# prism.net
KiCad netlist of a schematic drawn in EAGLE
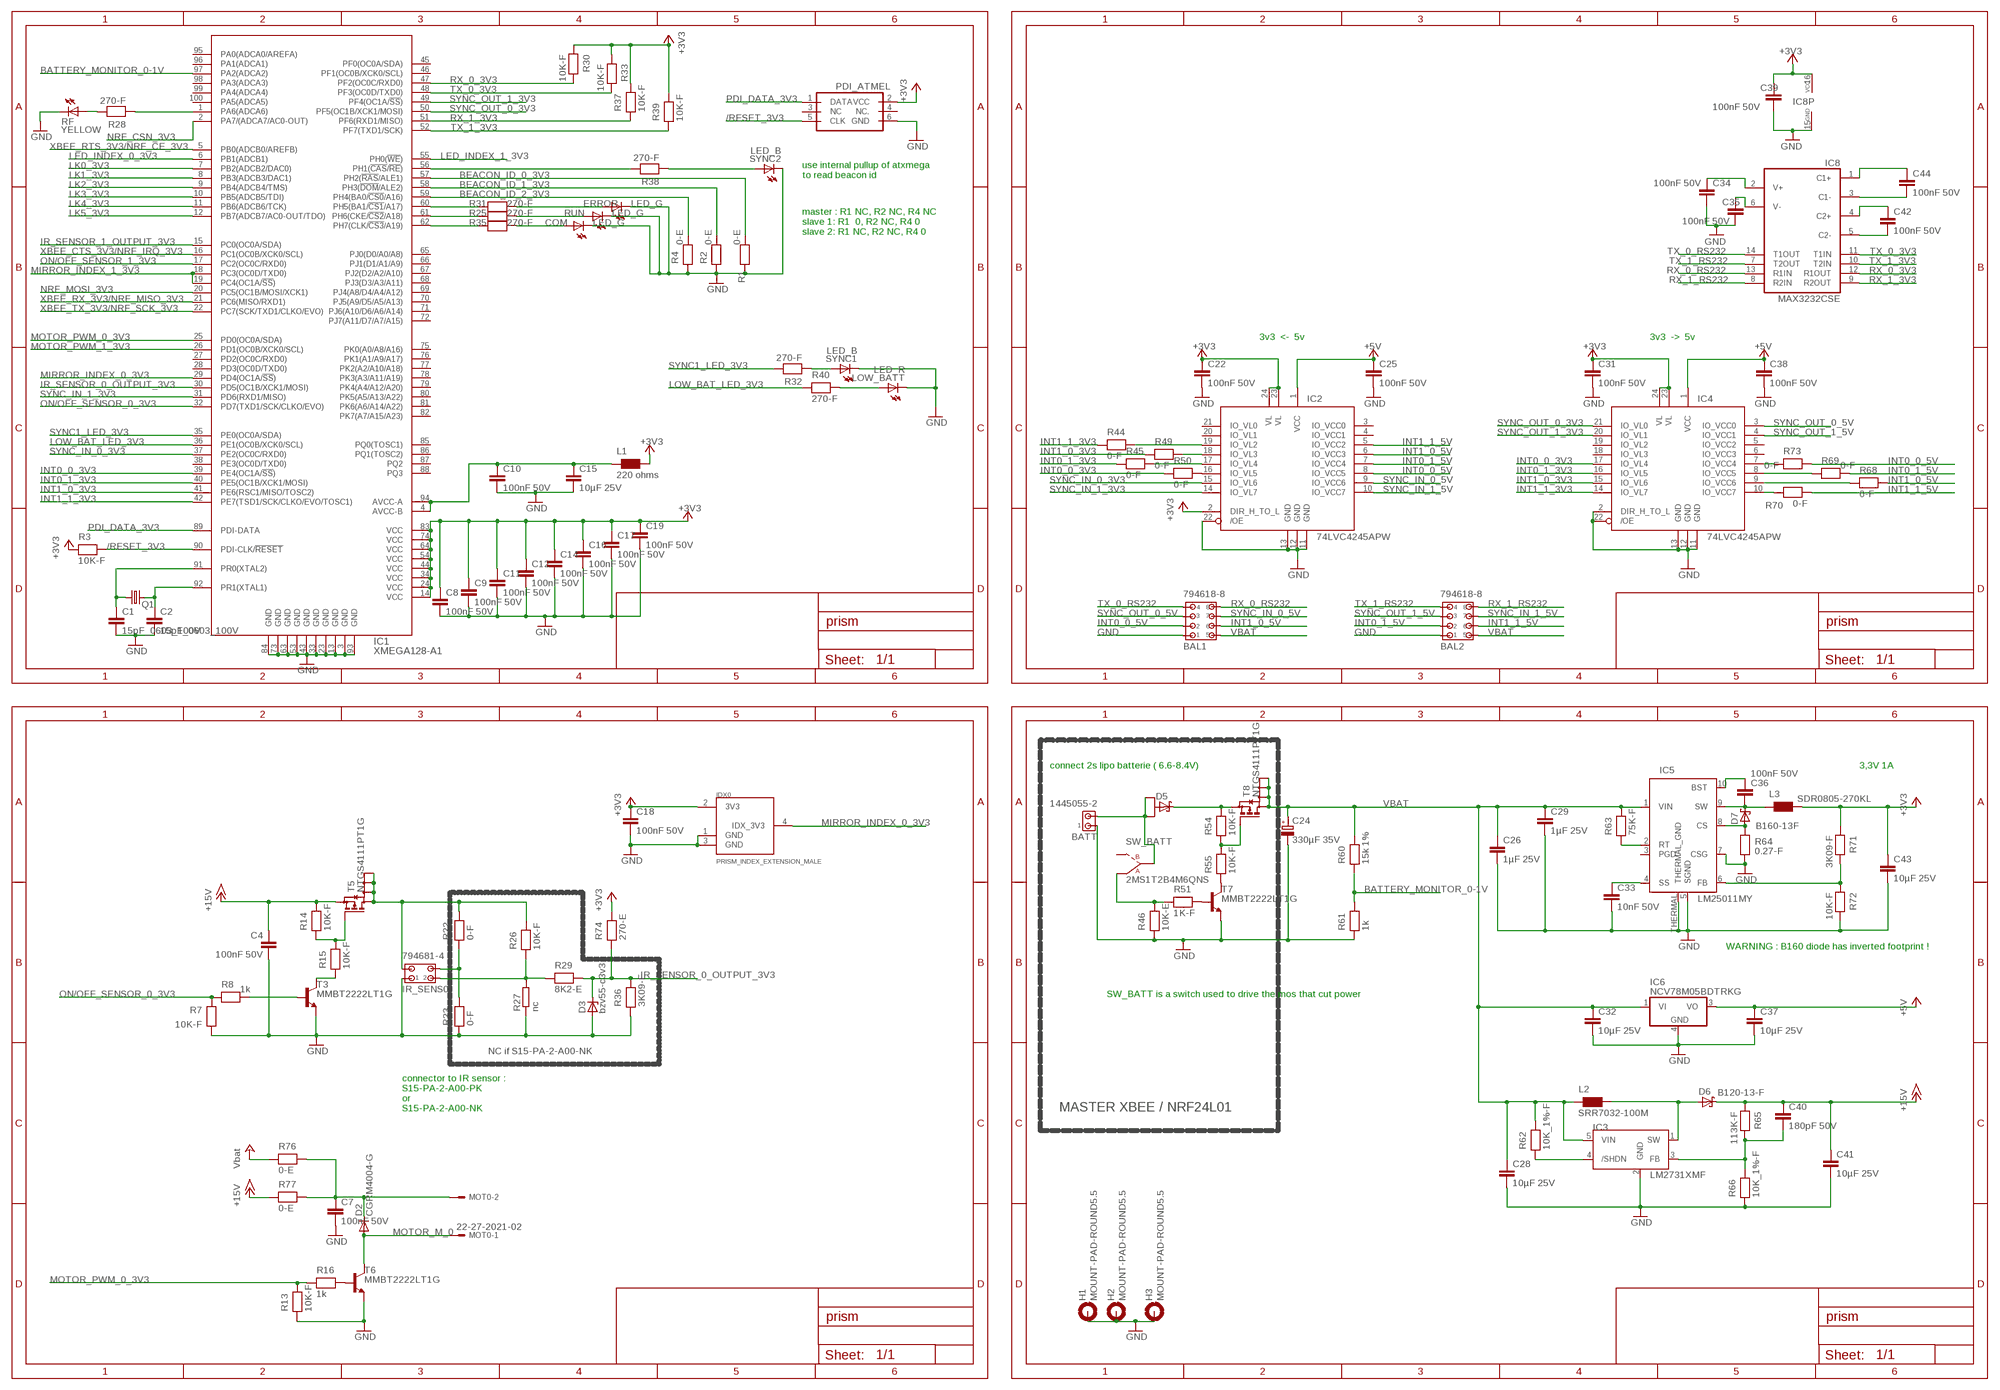
[diagram p0: schematic, sheet 1, part 1 of 2]
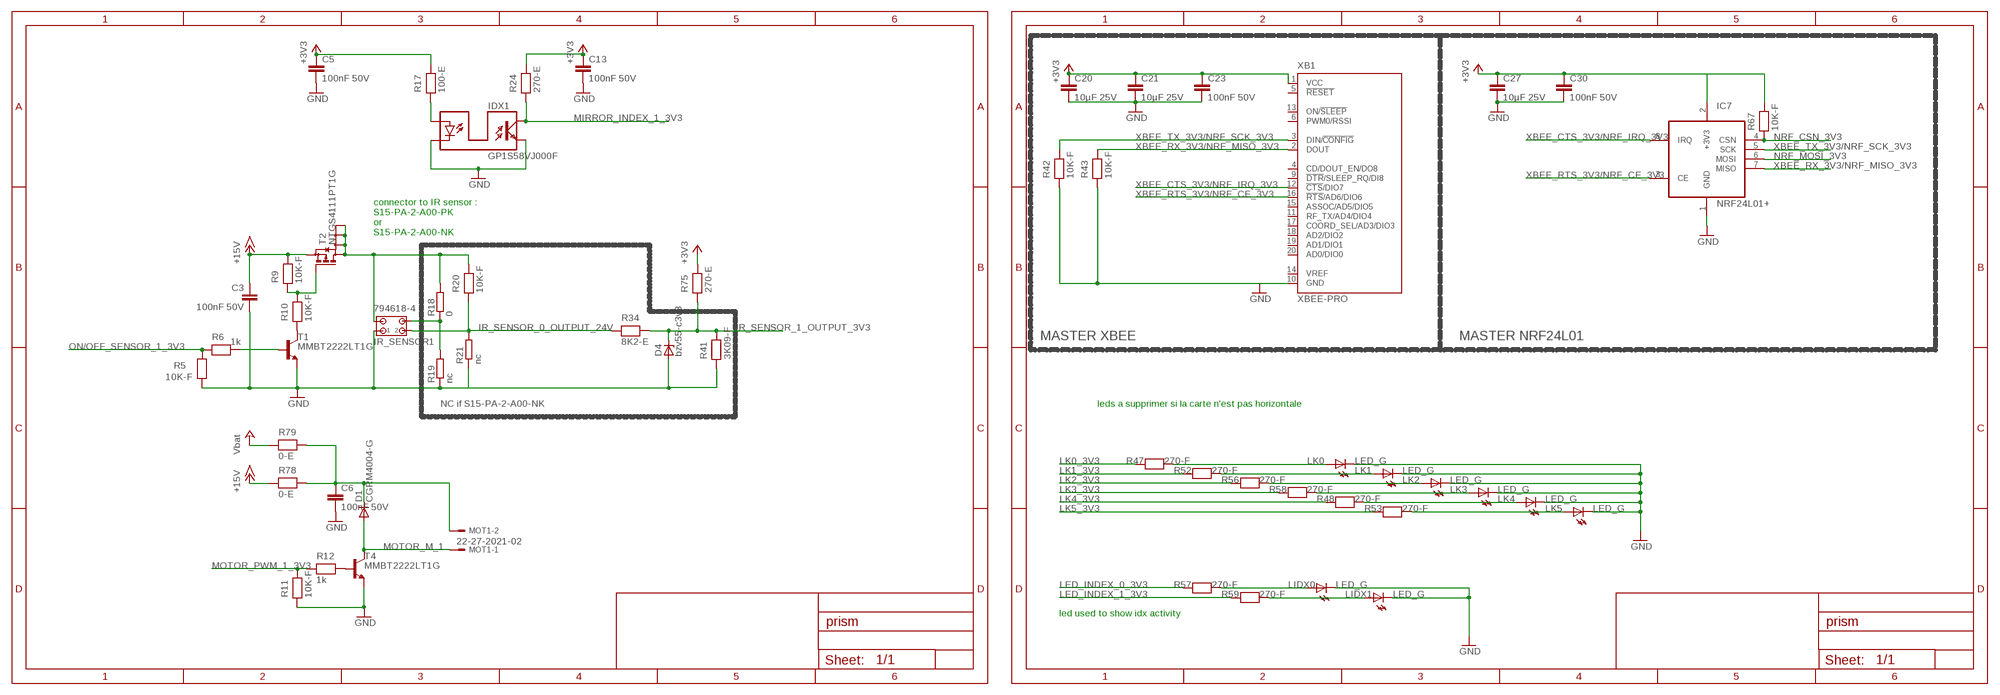
[diagram p1: schematic, sheet 1, part 2 of 2]

(export (version "E")
  (design (tool "Eeschema 10.0.6"))
  (components
    (comp (ref "BAL1")
      (value "794618-8")
      (footprint "eagle-import:794618-8")
      (libsource (lib "eagle-import") (part "794618-8"))
    )
    (comp (ref "BAL2")
      (value "794618-8")
      (footprint "eagle-import:794618-8")
      (libsource (lib "eagle-import") (part "794618-8"))
    )
    (comp (ref "BATT")
      (value "1445055-2")
      (footprint "eagle-import:1445055-2")
      (libsource (lib "eagle-import") (part "1445055-2"))
    )
    (comp (ref "C1")
      (value "15pF_0603_100V")
      (footprint "eagle-import:C0603")
      (libsource (lib "eagle-import") (part "15PF-F"))
    )
    (comp (ref "C2")
      (value "15pF_0603_100V")
      (footprint "eagle-import:C0603")
      (libsource (lib "eagle-import") (part "15PF-F"))
    )
    (comp (ref "C3")
      (value "100nF 50V")
      (footprint "eagle-import:C0603")
      (libsource (lib "eagle-import") (part "100NF-F"))
    )
    (comp (ref "C4")
      (value "100nF 50V")
      (footprint "eagle-import:C0603")
      (libsource (lib "eagle-import") (part "100NF-F"))
    )
    (comp (ref "C5")
      (value "100nF 50V")
      (footprint "eagle-import:C0603")
      (libsource (lib "eagle-import") (part "100NF-F"))
    )
    (comp (ref "C6")
      (value "100nF 50V")
      (footprint "eagle-import:C0603")
      (libsource (lib "eagle-import") (part "100NF-F"))
    )
    (comp (ref "C7")
      (value "100nF 50V")
      (footprint "eagle-import:C0603")
      (libsource (lib "eagle-import") (part "100NF-F"))
    )
    (comp (ref "C8")
      (value "100nF 50V")
      (footprint "eagle-import:C0603")
      (libsource (lib "eagle-import") (part "100NF-F"))
    )
    (comp (ref "C9")
      (value "100nF 50V")
      (footprint "eagle-import:C0603")
      (libsource (lib "eagle-import") (part "100NF-F"))
    )
    (comp (ref "C10")
      (value "100nF 50V")
      (footprint "eagle-import:C0603")
      (libsource (lib "eagle-import") (part "100NF-F"))
    )
    (comp (ref "C11")
      (value "100nF 50V")
      (footprint "eagle-import:C0603")
      (libsource (lib "eagle-import") (part "100NF-F"))
    )
    (comp (ref "C12")
      (value "100nF 50V")
      (footprint "eagle-import:C0603")
      (libsource (lib "eagle-import") (part "100NF-F"))
    )
    (comp (ref "C13")
      (value "100nF 50V")
      (footprint "eagle-import:C0603")
      (libsource (lib "eagle-import") (part "100NF-F"))
    )
    (comp (ref "C14")
      (value "100nF 50V")
      (footprint "eagle-import:C0603")
      (libsource (lib "eagle-import") (part "100NF-F"))
    )
    (comp (ref "C15")
      (value "10µF 25V")
      (footprint "eagle-import:C1210")
      (libsource (lib "eagle-import") (part "10UF-C_25V"))
    )
    (comp (ref "C16")
      (value "100nF 50V")
      (footprint "eagle-import:C0603")
      (libsource (lib "eagle-import") (part "100NF-F"))
    )
    (comp (ref "C17")
      (value "100nF 50V")
      (footprint "eagle-import:C0603")
      (libsource (lib "eagle-import") (part "100NF-F"))
    )
    (comp (ref "C18")
      (value "100nF 50V")
      (footprint "eagle-import:C0603")
      (libsource (lib "eagle-import") (part "100NF-F"))
    )
    (comp (ref "C19")
      (value "100nF 50V")
      (footprint "eagle-import:C0603")
      (libsource (lib "eagle-import") (part "100NF-F"))
    )
    (comp (ref "C20")
      (value "10µF 25V")
      (footprint "eagle-import:C1210")
      (libsource (lib "eagle-import") (part "10UF-C_25V"))
    )
    (comp (ref "C21")
      (value "10µF 25V")
      (footprint "eagle-import:C1210")
      (libsource (lib "eagle-import") (part "10UF-C_25V"))
    )
    (comp (ref "C22")
      (value "100nF 50V")
      (footprint "eagle-import:C0603")
      (libsource (lib "eagle-import") (part "100NF-F"))
    )
    (comp (ref "C23")
      (value "100nF 50V")
      (footprint "eagle-import:C0603")
      (libsource (lib "eagle-import") (part "100NF-F"))
    )
    (comp (ref "C24")
      (value "330µF 35V")
      (footprint "eagle-import:PANASONIC_G")
      (fields (field (name "MANUFACTURER") "EEEFK1V331P"))
      (libsource (lib "eagle-import") (part "330UF"))
    )
    (comp (ref "C25")
      (value "100nF 50V")
      (footprint "eagle-import:C0603")
      (libsource (lib "eagle-import") (part "100NF-F"))
    )
    (comp (ref "C26")
      (value "1µF 25V")
      (footprint "eagle-import:C1206")
      (libsource (lib "eagle-import") (part "1UFD_25V"))
    )
    (comp (ref "C27")
      (value "10µF 25V")
      (footprint "eagle-import:C1210")
      (libsource (lib "eagle-import") (part "10UF-C_25V"))
    )
    (comp (ref "C28")
      (value "10µF 25V")
      (footprint "eagle-import:C1210")
      (libsource (lib "eagle-import") (part "10UF-C_25V"))
    )
    (comp (ref "C29")
      (value "1µF 25V")
      (footprint "eagle-import:C1206")
      (libsource (lib "eagle-import") (part "1UFD_25V"))
    )
    (comp (ref "C30")
      (value "100nF 50V")
      (footprint "eagle-import:C0603")
      (libsource (lib "eagle-import") (part "100NF-F"))
    )
    (comp (ref "C31")
      (value "100nF 50V")
      (footprint "eagle-import:C0603")
      (libsource (lib "eagle-import") (part "100NF-F"))
    )
    (comp (ref "C32")
      (value "10µF 25V")
      (footprint "eagle-import:C1210")
      (libsource (lib "eagle-import") (part "10UF-C_25V"))
    )
    (comp (ref "C33")
      (value "10nF 50V")
      (footprint "eagle-import:C0603")
      (libsource (lib "eagle-import") (part "10NF-F"))
    )
    (comp (ref "C34")
      (value "100nF 50V")
      (footprint "eagle-import:C0603")
      (libsource (lib "eagle-import") (part "100NF-F"))
    )
    (comp (ref "C35")
      (value "100nF 50V")
      (footprint "eagle-import:C0603")
      (libsource (lib "eagle-import") (part "100NF-F"))
    )
    (comp (ref "C36")
      (value "100nF 50V")
      (footprint "eagle-import:C0603")
      (libsource (lib "eagle-import") (part "100NF-F"))
    )
    (comp (ref "C37")
      (value "10µF 25V")
      (footprint "eagle-import:C1210")
      (libsource (lib "eagle-import") (part "10UF-C_25V"))
    )
    (comp (ref "C38")
      (value "100nF 50V")
      (footprint "eagle-import:C0603")
      (libsource (lib "eagle-import") (part "100NF-F"))
    )
    (comp (ref "C39")
      (value "100nF 50V")
      (footprint "eagle-import:C0603")
      (libsource (lib "eagle-import") (part "100NF-F"))
    )
    (comp (ref "C40")
      (value "180pF 50V")
      (footprint "eagle-import:C0603")
      (libsource (lib "eagle-import") (part "180PF-F"))
    )
    (comp (ref "C41")
      (value "10µF 25V")
      (footprint "eagle-import:C1210")
      (libsource (lib "eagle-import") (part "10UF-C_25V"))
    )
    (comp (ref "C42")
      (value "100nF 50V")
      (footprint "eagle-import:C0603")
      (libsource (lib "eagle-import") (part "100NF-F"))
    )
    (comp (ref "C43")
      (value "10µF 25V")
      (footprint "eagle-import:C1210")
      (libsource (lib "eagle-import") (part "10UF-C_25V"))
    )
    (comp (ref "C44")
      (value "100nF 50V")
      (footprint "eagle-import:C0603")
      (libsource (lib "eagle-import") (part "100NF-F"))
    )
    (comp (ref "COM")
      (value "LED_G")
      (footprint "eagle-import:CHIP-LED0805")
      (libsource (lib "eagle-import") (part "LED_G"))
    )
    (comp (ref "D1")
      (value "CGRM4004-G")
      (footprint "eagle-import:SOD-123_MINI-SMA")
      (libsource (lib "eagle-import") (part "CGRM400-G4"))
    )
    (comp (ref "D2")
      (value "CGRM4004-G")
      (footprint "eagle-import:SOD-123_MINI-SMA")
      (libsource (lib "eagle-import") (part "CGRM400-G4"))
    )
    (comp (ref "D3")
      (value "bzv55-c3v3")
      (footprint "eagle-import:SOD80C")
      (libsource (lib "eagle-import") (part "BZV55-C3V3SOD80C"))
    )
    (comp (ref "D4")
      (value "bzv55-c3v3")
      (footprint "eagle-import:SOD80C")
      (libsource (lib "eagle-import") (part "BZV55-C3V3SOD80C"))
    )
    (comp (ref "D5")
      (value "50WQ03")
      (footprint "eagle-import:TO252")
      (libsource (lib "eagle-import") (part "50WQ03"))
    )
    (comp (ref "D6")
      (value "B120-13-F")
      (footprint "eagle-import:SMB")
      (libsource (lib "eagle-import") (part "B120-13-F"))
    )
    (comp (ref "D7")
      (value "B160-13F")
      (footprint "eagle-import:SMA")
      (libsource (lib "eagle-import") (part "B160-13F"))
    )
    (comp (ref "ERROR")
      (value "LED_G")
      (footprint "eagle-import:CHIP-LED0805")
      (libsource (lib "eagle-import") (part "LED_G"))
    )
    (comp (ref "H1")
      (value "MOUNT-PAD-ROUND5.5")
      (footprint "eagle-import:5,5-PAD")
      (libsource (lib "eagle-import") (part "MOUNT-PAD-ROUND5.5"))
    )
    (comp (ref "H2")
      (value "MOUNT-PAD-ROUND5.5")
      (footprint "eagle-import:5,5-PAD")
      (libsource (lib "eagle-import") (part "MOUNT-PAD-ROUND5.5"))
    )
    (comp (ref "H3")
      (value "MOUNT-PAD-ROUND5.5")
      (footprint "eagle-import:5,5-PAD")
      (libsource (lib "eagle-import") (part "MOUNT-PAD-ROUND5.5"))
    )
    (comp (ref "IC1")
      (value "XMEGA128-A1")
      (footprint "eagle-import:TQFP100")
      (libsource (lib "eagle-import") (part "XMEGA-A1TQFP"))
    )
    (comp (ref "IC2")
      (value "74LVC4245APW")
      (footprint "eagle-import:TSSOP24")
      (libsource (lib "eagle-import") (part "74LVC4245APW"))
    )
    (comp (ref "IC3")
      (value "LM2731XMF")
      (footprint "eagle-import:SOT23-5")
      (libsource (lib "eagle-import") (part "LM2731XMF"))
    )
    (comp (ref "IC4")
      (value "74LVC4245APW")
      (footprint "eagle-import:TSSOP24")
      (libsource (lib "eagle-import") (part "74LVC4245APW"))
    )
    (comp (ref "IC5")
      (value "LM25011MY")
      (footprint "eagle-import:MSOP10_THERMAL")
      (libsource (lib "eagle-import") (part "LM25011MY"))
    )
    (comp (ref "IC6")
      (value "NCV78M05BDTRKG")
      (footprint "eagle-import:DPACK_3")
      (libsource (lib "eagle-import") (part "NCV78M05BDTRKG"))
    )
    (comp (ref "IC7")
      (value "NRF24L01+")
      (footprint "eagle-import:NRF24L01+")
      (libsource (lib "eagle-import") (part "NRF24L01+"))
    )
    (comp (ref "IC8")
      (value "MAX3232CSE")
      (footprint "eagle-import:SO16")
      (libsource (lib "eagle-import") (part "MAX3232SEC"))
    )
    (comp (ref "IDX0")
      (value "PRISM_INDEX_EXTENSION_MALE")
      (footprint "eagle-import:PRISM_INDEX_EXTENSION_MALE")
      (libsource (lib "eagle-import") (part "PRISM_INDEX_EXTENSION_MALE"))
    )
    (comp (ref "IDX1")
      (value "GP1S58VJ000F")
      (footprint "eagle-import:GP1S58VJ000F")
      (libsource (lib "eagle-import") (part "GP1S58VJ000F"))
    )
    (comp (ref "IR_SENS0")
      (value "794681-4")
      (footprint "eagle-import:794681-4")
      (libsource (lib "eagle-import") (part "794681-4"))
    )
    (comp (ref "IR_SENSOR1")
      (value "794618-4")
      (footprint "eagle-import:794618-4")
      (libsource (lib "eagle-import") (part "794618-4"))
    )
    (comp (ref "L1")
      (value "220 ohms")
      (footprint "eagle-import:R0603")
      (libsource (lib "eagle-import") (part "FERRITE_220OHMS"))
    )
    (comp (ref "L2")
      (value "SRR7032-100M")
      (footprint "eagle-import:SRR7032")
      (libsource (lib "eagle-import") (part "SRR7032-100M"))
    )
    (comp (ref "L3")
      (value "SDR0805-270KL")
      (footprint "eagle-import:SDR0805")
      (libsource (lib "eagle-import") (part "SDR0805-270KL"))
    )
    (comp (ref "LIDX0")
      (value "LED_G")
      (footprint "eagle-import:CHIP-LED0805")
      (libsource (lib "eagle-import") (part "LED_G"))
    )
    (comp (ref "LIDX1")
      (value "LED_G")
      (footprint "eagle-import:CHIP-LED0805")
      (libsource (lib "eagle-import") (part "LED_G"))
    )
    (comp (ref "LK0")
      (value "LED_G")
      (footprint "eagle-import:CHIP-LED0805")
      (libsource (lib "eagle-import") (part "LED_G"))
    )
    (comp (ref "LK1")
      (value "LED_G")
      (footprint "eagle-import:CHIP-LED0805")
      (libsource (lib "eagle-import") (part "LED_G"))
    )
    (comp (ref "LK2")
      (value "LED_G")
      (footprint "eagle-import:CHIP-LED0805")
      (libsource (lib "eagle-import") (part "LED_G"))
    )
    (comp (ref "LK3")
      (value "LED_G")
      (footprint "eagle-import:CHIP-LED0805")
      (libsource (lib "eagle-import") (part "LED_G"))
    )
    (comp (ref "LK4")
      (value "LED_G")
      (footprint "eagle-import:CHIP-LED0805")
      (libsource (lib "eagle-import") (part "LED_G"))
    )
    (comp (ref "LK5")
      (value "LED_G")
      (footprint "eagle-import:CHIP-LED0805")
      (libsource (lib "eagle-import") (part "LED_G"))
    )
    (comp (ref "LOW_BATT")
      (value "LED_R")
      (footprint "eagle-import:CHIP-LED0805")
      (libsource (lib "eagle-import") (part "LED_R"))
    )
    (comp (ref "MOT0")
      (value "22-27-2021-02")
      (footprint "eagle-import:6410-02")
      (libsource (lib "eagle-import") (part "22-?-0227-2021"))
    )
    (comp (ref "MOT1")
      (value "22-27-2021-02")
      (footprint "eagle-import:6410-02")
      (libsource (lib "eagle-import") (part "22-?-0227-2021"))
    )
    (comp (ref "PDI_ATMEL")
      (value "PDI_ATMELL")
      (footprint "eagle-import:ML6L")
      (libsource (lib "eagle-import") (part "PDI_ATMELL"))
    )
    (comp (ref "Q1")
      (value "CRYSTAL_16MHZ_HC49UP")
      (footprint "eagle-import:HC49UP")
      (libsource (lib "eagle-import") (part "CRYSTAL_16MHZ_HC49UP"))
    )
    (comp (ref "R1")
      (value "0-E")
      (footprint "eagle-import:R0805")
      (libsource (lib "eagle-import") (part "0-E"))
    )
    (comp (ref "R2")
      (value "0-E")
      (footprint "eagle-import:R0805")
      (libsource (lib "eagle-import") (part "0-E"))
    )
    (comp (ref "R3")
      (value "10K-F")
      (footprint "eagle-import:R0603")
      (libsource (lib "eagle-import") (part "10K-F"))
    )
    (comp (ref "R4")
      (value "0-E")
      (footprint "eagle-import:R0805")
      (libsource (lib "eagle-import") (part "0-E"))
    )
    (comp (ref "R5")
      (value "10K-F")
      (footprint "eagle-import:R0603")
      (libsource (lib "eagle-import") (part "10K-F"))
    )
    (comp (ref "R6")
      (value "1k")
      (footprint "eagle-import:R0603")
      (libsource (lib "eagle-import") (part "1K-F"))
    )
    (comp (ref "R7")
      (value "10K-F")
      (footprint "eagle-import:R0603")
      (libsource (lib "eagle-import") (part "10K-F"))
    )
    (comp (ref "R8")
      (value "1k")
      (footprint "eagle-import:R0603")
      (libsource (lib "eagle-import") (part "1K-F"))
    )
    (comp (ref "R9")
      (value "10K-F")
      (footprint "eagle-import:R0603")
      (libsource (lib "eagle-import") (part "10K-F"))
    )
    (comp (ref "R10")
      (value "10K-F")
      (footprint "eagle-import:R0603")
      (libsource (lib "eagle-import") (part "10K-F"))
    )
    (comp (ref "R11")
      (value "10K-F")
      (footprint "eagle-import:R0603")
      (libsource (lib "eagle-import") (part "10K-F"))
    )
    (comp (ref "R12")
      (value "1k")
      (footprint "eagle-import:R0603")
      (libsource (lib "eagle-import") (part "1K-F"))
    )
    (comp (ref "R13")
      (value "10K-F")
      (footprint "eagle-import:R0603")
      (libsource (lib "eagle-import") (part "10K-F"))
    )
    (comp (ref "R14")
      (value "10K-F")
      (footprint "eagle-import:R0603")
      (libsource (lib "eagle-import") (part "10K-F"))
    )
    (comp (ref "R15")
      (value "10K-F")
      (footprint "eagle-import:R0603")
      (libsource (lib "eagle-import") (part "10K-F"))
    )
    (comp (ref "R16")
      (value "1k")
      (footprint "eagle-import:R0603")
      (libsource (lib "eagle-import") (part "1K-F"))
    )
    (comp (ref "R17")
      (value "100-E")
      (footprint "eagle-import:R0805")
      (libsource (lib "eagle-import") (part "100-E"))
    )
    (comp (ref "R18")
      (value "0")
      (footprint "eagle-import:R0603")
      (libsource (lib "eagle-import") (part "R-EU_R0603"))
    )
    (comp (ref "R19")
      (value "nc")
      (footprint "eagle-import:R0603")
      (libsource (lib "eagle-import") (part "R-EU_R0603"))
    )
    (comp (ref "R20")
      (value "10K-F")
      (footprint "eagle-import:R0603")
      (libsource (lib "eagle-import") (part "10K-F"))
    )
    (comp (ref "R21")
      (value "nc")
      (footprint "eagle-import:R0603")
      (libsource (lib "eagle-import") (part "R-EU_R0603"))
    )
    (comp (ref "R22")
      (value "0-F")
      (footprint "eagle-import:R0603")
      (libsource (lib "eagle-import") (part "0-F"))
    )
    (comp (ref "R23")
      (value "0-F")
      (footprint "eagle-import:R0603")
      (libsource (lib "eagle-import") (part "0-F"))
    )
    (comp (ref "R24")
      (value "270-E")
      (footprint "eagle-import:R0805")
      (libsource (lib "eagle-import") (part "270-E"))
    )
    (comp (ref "R25")
      (value "270-F")
      (footprint "eagle-import:R0603")
      (libsource (lib "eagle-import") (part "270-F"))
    )
    (comp (ref "R26")
      (value "10K-F")
      (footprint "eagle-import:R0603")
      (libsource (lib "eagle-import") (part "10K-F"))
    )
    (comp (ref "R27")
      (value "nc")
      (footprint "eagle-import:R0603")
      (libsource (lib "eagle-import") (part "R-EU_R0603"))
    )
    (comp (ref "R28")
      (value "270-F")
      (footprint "eagle-import:R0603")
      (libsource (lib "eagle-import") (part "270-F"))
    )
    (comp (ref "R29")
      (value "8K2-E")
      (footprint "eagle-import:R0805")
      (libsource (lib "eagle-import") (part "8K2-E"))
    )
    (comp (ref "R30")
      (value "10K-F")
      (footprint "eagle-import:R0603")
      (libsource (lib "eagle-import") (part "10K-F"))
    )
    (comp (ref "R31")
      (value "270-F")
      (footprint "eagle-import:R0603")
      (libsource (lib "eagle-import") (part "270-F"))
    )
    (comp (ref "R32")
      (value "270-F")
      (footprint "eagle-import:R0603")
      (libsource (lib "eagle-import") (part "270-F"))
    )
    (comp (ref "R33")
      (value "10K-F")
      (footprint "eagle-import:R0603")
      (libsource (lib "eagle-import") (part "10K-F"))
    )
    (comp (ref "R34")
      (value "8K2-E")
      (footprint "eagle-import:R0805")
      (libsource (lib "eagle-import") (part "8K2-E"))
    )
    (comp (ref "R35")
      (value "270-F")
      (footprint "eagle-import:R0603")
      (libsource (lib "eagle-import") (part "270-F"))
    )
    (comp (ref "R36")
      (value "3K09-F")
      (footprint "eagle-import:R0603")
      (libsource (lib "eagle-import") (part "3K09-F"))
    )
    (comp (ref "R37")
      (value "10K-F")
      (footprint "eagle-import:R0603")
      (libsource (lib "eagle-import") (part "10K-F"))
    )
    (comp (ref "R38")
      (value "270-F")
      (footprint "eagle-import:R0603")
      (libsource (lib "eagle-import") (part "270-F"))
    )
    (comp (ref "R39")
      (value "10K-F")
      (footprint "eagle-import:R0603")
      (libsource (lib "eagle-import") (part "10K-F"))
    )
    (comp (ref "R40")
      (value "270-F")
      (footprint "eagle-import:R0603")
      (libsource (lib "eagle-import") (part "270-F"))
    )
    (comp (ref "R41")
      (value "3K09-F")
      (footprint "eagle-import:R0603")
      (libsource (lib "eagle-import") (part "3K09-F"))
    )
    (comp (ref "R42")
      (value "10K-F")
      (footprint "eagle-import:R0603")
      (libsource (lib "eagle-import") (part "10K-F"))
    )
    (comp (ref "R43")
      (value "10K-F")
      (footprint "eagle-import:R0603")
      (libsource (lib "eagle-import") (part "10K-F"))
    )
    (comp (ref "R44")
      (value "0-F")
      (footprint "eagle-import:R0603")
      (libsource (lib "eagle-import") (part "0-F"))
    )
    (comp (ref "R45")
      (value "0-F")
      (footprint "eagle-import:R0603")
      (libsource (lib "eagle-import") (part "0-F"))
    )
    (comp (ref "R46")
      (value "10K-E")
      (footprint "eagle-import:R0805")
      (libsource (lib "eagle-import") (part "10K-E"))
    )
    (comp (ref "R47")
      (value "270-F")
      (footprint "eagle-import:R0603")
      (libsource (lib "eagle-import") (part "270-F"))
    )
    (comp (ref "R48")
      (value "270-F")
      (footprint "eagle-import:R0603")
      (libsource (lib "eagle-import") (part "270-F"))
    )
    (comp (ref "R49")
      (value "0-F")
      (footprint "eagle-import:R0603")
      (libsource (lib "eagle-import") (part "0-F"))
    )
    (comp (ref "R50")
      (value "0-F")
      (footprint "eagle-import:R0603")
      (libsource (lib "eagle-import") (part "0-F"))
    )
    (comp (ref "R51")
      (value "1K-F")
      (footprint "eagle-import:R0603")
      (libsource (lib "eagle-import") (part "1K-F"))
    )
    (comp (ref "R52")
      (value "270-F")
      (footprint "eagle-import:R0603")
      (libsource (lib "eagle-import") (part "270-F"))
    )
    (comp (ref "R53")
      (value "270-F")
      (footprint "eagle-import:R0603")
      (libsource (lib "eagle-import") (part "270-F"))
    )
    (comp (ref "R54")
      (value "10K-F")
      (footprint "eagle-import:R0603")
      (libsource (lib "eagle-import") (part "10K-F"))
    )
    (comp (ref "R55")
      (value "10K-F")
      (footprint "eagle-import:R0603")
      (libsource (lib "eagle-import") (part "10K-F"))
    )
    (comp (ref "R56")
      (value "270-F")
      (footprint "eagle-import:R0603")
      (libsource (lib "eagle-import") (part "270-F"))
    )
    (comp (ref "R57")
      (value "270-F")
      (footprint "eagle-import:R0603")
      (libsource (lib "eagle-import") (part "270-F"))
    )
    (comp (ref "R58")
      (value "270-F")
      (footprint "eagle-import:R0603")
      (libsource (lib "eagle-import") (part "270-F"))
    )
    (comp (ref "R59")
      (value "270-F")
      (footprint "eagle-import:R0603")
      (libsource (lib "eagle-import") (part "270-F"))
    )
    (comp (ref "R60")
      (value "15k 1%")
      (footprint "eagle-import:R0805")
      (libsource (lib "eagle-import") (part "15K-E"))
    )
    (comp (ref "R61")
      (value "1k")
      (footprint "eagle-import:R0805")
      (libsource (lib "eagle-import") (part "1K-E"))
    )
    (comp (ref "R62")
      (value "10K_1%-F")
      (footprint "eagle-import:R0603")
      (libsource (lib "eagle-import") (part "10K_1%-F"))
    )
    (comp (ref "R63")
      (value "75K-F")
      (footprint "eagle-import:R0603")
      (libsource (lib "eagle-import") (part "75K-F"))
    )
    (comp (ref "R64")
      (value "0.27-F")
      (footprint "eagle-import:R0603")
      (libsource (lib "eagle-import") (part "0.27-F"))
    )
    (comp (ref "R65")
      (value "113K-F")
      (footprint "eagle-import:R0603")
      (libsource (lib "eagle-import") (part "113K-F"))
    )
    (comp (ref "R66")
      (value "10K_1%-F")
      (footprint "eagle-import:R0603")
      (libsource (lib "eagle-import") (part "10K_1%-F"))
    )
    (comp (ref "R67")
      (value "10K-F")
      (footprint "eagle-import:R0603")
      (libsource (lib "eagle-import") (part "10K-F"))
    )
    (comp (ref "R68")
      (value "0-F")
      (footprint "eagle-import:R0603")
      (libsource (lib "eagle-import") (part "0-F"))
    )
    (comp (ref "R69")
      (value "0-F")
      (footprint "eagle-import:R0603")
      (libsource (lib "eagle-import") (part "0-F"))
    )
    (comp (ref "R70")
      (value "0-F")
      (footprint "eagle-import:R0603")
      (libsource (lib "eagle-import") (part "0-F"))
    )
    (comp (ref "R71")
      (value "3K09-F")
      (footprint "eagle-import:R0603")
      (libsource (lib "eagle-import") (part "3K09-F"))
    )
    (comp (ref "R72")
      (value "10K-F")
      (footprint "eagle-import:R0603")
      (libsource (lib "eagle-import") (part "10K-F"))
    )
    (comp (ref "R73")
      (value "0-F")
      (footprint "eagle-import:R0603")
      (libsource (lib "eagle-import") (part "0-F"))
    )
    (comp (ref "R74")
      (value "270-E")
      (footprint "eagle-import:R0805")
      (libsource (lib "eagle-import") (part "270-E"))
    )
    (comp (ref "R75")
      (value "270-E")
      (footprint "eagle-import:R0805")
      (libsource (lib "eagle-import") (part "270-E"))
    )
    (comp (ref "R76")
      (value "0-E")
      (footprint "eagle-import:R0805")
      (libsource (lib "eagle-import") (part "0-E"))
    )
    (comp (ref "R77")
      (value "0-E")
      (footprint "eagle-import:R0805")
      (libsource (lib "eagle-import") (part "0-E"))
    )
    (comp (ref "R78")
      (value "0-E")
      (footprint "eagle-import:R0805")
      (libsource (lib "eagle-import") (part "0-E"))
    )
    (comp (ref "R79")
      (value "0-E")
      (footprint "eagle-import:R0805")
      (libsource (lib "eagle-import") (part "0-E"))
    )
    (comp (ref "RF")
      (value "YELLOW")
      (footprint "eagle-import:CHIP-LED0805")
      (libsource (lib "eagle-import") (part "LED_Y"))
    )
    (comp (ref "RUN")
      (value "LED_G")
      (footprint "eagle-import:CHIP-LED0805")
      (libsource (lib "eagle-import") (part "LED_G"))
    )
    (comp (ref "SW_BATT")
      (value "2MS1T2B4M6QNS")
      (footprint "eagle-import:2MS1T2B4M6QNS")
      (libsource (lib "eagle-import") (part "2MS1T2B4M6QNS"))
    )
    (comp (ref "SYNC1")
      (value "LED_B")
      (footprint "eagle-import:CHIP-LED0805")
      (libsource (lib "eagle-import") (part "LED_B"))
    )
    (comp (ref "SYNC2")
      (value "LED_B")
      (footprint "eagle-import:CHIP-LED0805")
      (libsource (lib "eagle-import") (part "LED_B"))
    )
    (comp (ref "T1")
      (value "MMBT2222LT1G")
      (footprint "eagle-import:SOT23-BEC")
      (libsource (lib "eagle-import") (part "-NPN-SOT23-BECMMBT2222ALT1"))
    )
    (comp (ref "T2")
      (value "NTGS4111PT1G")
      (footprint "eagle-import:TSOP-6")
      (libsource (lib "eagle-import") (part "NTGS4111PT1G"))
    )
    (comp (ref "T3")
      (value "MMBT2222LT1G")
      (footprint "eagle-import:SOT23-BEC")
      (libsource (lib "eagle-import") (part "-NPN-SOT23-BECMMBT2222ALT1"))
    )
    (comp (ref "T4")
      (value "MMBT2222LT1G")
      (footprint "eagle-import:SOT23-BEC")
      (libsource (lib "eagle-import") (part "-NPN-SOT23-BECMMBT2222ALT1"))
    )
    (comp (ref "T5")
      (value "NTGS4111PT1G")
      (footprint "eagle-import:TSOP-6")
      (libsource (lib "eagle-import") (part "NTGS4111PT1G"))
    )
    (comp (ref "T6")
      (value "MMBT2222LT1G")
      (footprint "eagle-import:SOT23-BEC")
      (libsource (lib "eagle-import") (part "-NPN-SOT23-BECMMBT2222ALT1"))
    )
    (comp (ref "T7")
      (value "MMBT2222LT1G")
      (footprint "eagle-import:SOT23-BEC")
      (libsource (lib "eagle-import") (part "-NPN-SOT23-BECMMBT2222ALT1"))
    )
    (comp (ref "T8")
      (value "NTGS4111PT1G")
      (footprint "eagle-import:TSOP-6")
      (libsource (lib "eagle-import") (part "NTGS4111PT1G"))
    )
    (comp (ref "XB1")
      (value "XBEE-PRO")
      (footprint "eagle-import:XBEE-PRO")
      (fields (field (name "MPN") "XBP24-AWI-001"))
      (libsource (lib "eagle-import") (part "XBEE-PRO"))
    )
  )
  (nets
    (net (code "1") (name "+3V3") (class "Default")
      (node (ref "C11") (pin "1") (pinfunction "1_1") (pintype "passive"))
      (node (ref "C12") (pin "1") (pinfunction "1_1") (pintype "passive"))
      (node (ref "C13") (pin "1") (pinfunction "1_1") (pintype "passive"))
      (node (ref "C14") (pin "1") (pinfunction "1_1") (pintype "passive"))
      (node (ref "C16") (pin "1") (pinfunction "1_1") (pintype "passive"))
      (node (ref "C17") (pin "1") (pinfunction "1_1") (pintype "passive"))
      (node (ref "C18") (pin "1") (pinfunction "1_1") (pintype "passive"))
      (node (ref "C19") (pin "1") (pinfunction "1_1") (pintype "passive"))
      (node (ref "C20") (pin "1") (pinfunction "1_1") (pintype "passive"))
      (node (ref "C21") (pin "1") (pinfunction "1_1") (pintype "passive"))
      (node (ref "C22") (pin "1") (pinfunction "1_1") (pintype "passive"))
      (node (ref "C23") (pin "1") (pinfunction "1_1") (pintype "passive"))
      (node (ref "C27") (pin "1") (pinfunction "1_1") (pintype "passive"))
      (node (ref "C30") (pin "1") (pinfunction "1_1") (pintype "passive"))
      (node (ref "C31") (pin "1") (pinfunction "1_1") (pintype "passive"))
      (node (ref "C39") (pin "1") (pinfunction "1_1") (pintype "passive"))
      (node (ref "C43") (pin "1") (pinfunction "1_1") (pintype "passive"))
      (node (ref "C5") (pin "1") (pinfunction "1_1") (pintype "passive"))
      (node (ref "C8") (pin "1") (pinfunction "1_1") (pintype "passive"))
      (node (ref "C9") (pin "1") (pinfunction "1_1") (pintype "passive"))
      (node (ref "IC1") (pin "14") (pinfunction "VCC_14") (pintype "power_in"))
      (node (ref "IC1") (pin "24") (pinfunction "VCC_24") (pintype "power_in"))
      (node (ref "IC1") (pin "34") (pinfunction "VCC_34") (pintype "power_in"))
      (node (ref "IC1") (pin "44") (pinfunction "VCC_44") (pintype "power_in"))
      (node (ref "IC1") (pin "54") (pinfunction "VCC_54") (pintype "power_in"))
      (node (ref "IC1") (pin "64") (pinfunction "VCC_64") (pintype "power_in"))
      (node (ref "IC1") (pin "74") (pinfunction "VCC_74") (pintype "power_in"))
      (node (ref "IC1") (pin "83") (pinfunction "VCC_83") (pintype "power_in"))
      (node (ref "IC2") (pin "2") (pinfunction "DIR_H_TO_L_2") (pintype "bidirectional"))
      (node (ref "IC2") (pin "23") (pinfunction "VL_23") (pintype "power_in"))
      (node (ref "IC2") (pin "24") (pinfunction "VL_24") (pintype "power_in"))
      (node (ref "IC4") (pin "23") (pinfunction "VL_23") (pintype "power_in"))
      (node (ref "IC4") (pin "24") (pinfunction "VL_24") (pintype "power_in"))
      (node (ref "IC7") (pin "2") (pinfunction "+3V3_2") (pintype "bidirectional"))
      (node (ref "IC8") (pin "16") (pinfunction "VCC_16") (pintype "power_in"))
      (node (ref "IDX0") (pin "2") (pinfunction "3V3_2") (pintype "bidirectional"))
      (node (ref "L1") (pin "2") (pinfunction "2_2") (pintype "passive"))
      (node (ref "L3") (pin "2") (pinfunction "2_2") (pintype "passive"))
      (node (ref "PDI_ATMEL") (pin "2") (pinfunction "VCC_2") (pintype "passive"))
      (node (ref "R17") (pin "2") (pinfunction "2_2") (pintype "bidirectional"))
      (node (ref "R24") (pin "2") (pinfunction "2_2") (pintype "bidirectional"))
      (node (ref "R3") (pin "1") (pinfunction "1_1") (pintype "bidirectional"))
      (node (ref "R30") (pin "1") (pinfunction "1_1") (pintype "bidirectional"))
      (node (ref "R33") (pin "1") (pinfunction "1_1") (pintype "bidirectional"))
      (node (ref "R37") (pin "2") (pinfunction "2_2") (pintype "bidirectional"))
      (node (ref "R39") (pin "2") (pinfunction "2_2") (pintype "bidirectional"))
      (node (ref "R67") (pin "2") (pinfunction "2_2") (pintype "bidirectional"))
      (node (ref "R71") (pin "1") (pinfunction "1_1") (pintype "bidirectional"))
      (node (ref "R74") (pin "2") (pinfunction "2_2") (pintype "bidirectional"))
      (node (ref "R75") (pin "2") (pinfunction "2_2") (pintype "bidirectional"))
      (node (ref "XB1") (pin "1") (pinfunction "VCC_1") (pintype "power_in"))
    )
    (net (code "2") (name "+5V") (class "Default")
      (node (ref "C25") (pin "1") (pinfunction "1_1") (pintype "passive"))
      (node (ref "C37") (pin "1") (pinfunction "1_1") (pintype "passive"))
      (node (ref "C38") (pin "1") (pinfunction "1_1") (pintype "passive"))
      (node (ref "IC2") (pin "1") (pinfunction "VCC_1") (pintype "power_in"))
      (node (ref "IC4") (pin "1") (pinfunction "VCC_1") (pintype "power_in"))
      (node (ref "IC6") (pin "3") (pinfunction "VO_3") (pintype "passive"))
    )
    (net (code "3") (name "+15V") (class "Default")
      (node (ref "C3") (pin "1") (pinfunction "1_1") (pintype "passive"))
      (node (ref "C4") (pin "1") (pinfunction "1_1") (pintype "passive"))
      (node (ref "C40") (pin "1") (pinfunction "1_1") (pintype "passive"))
      (node (ref "C41") (pin "1") (pinfunction "1_1") (pintype "passive"))
      (node (ref "D6") (pin "C") (pinfunction "C_C") (pintype "passive"))
      (node (ref "R14") (pin "2") (pinfunction "2_2") (pintype "bidirectional"))
      (node (ref "R65") (pin "1") (pinfunction "1_1") (pintype "bidirectional"))
      (node (ref "R77") (pin "1") (pinfunction "1_1") (pintype "bidirectional"))
      (node (ref "R78") (pin "1") (pinfunction "1_1") (pintype "bidirectional"))
      (node (ref "R9") (pin "2") (pinfunction "2_2") (pintype "bidirectional"))
      (node (ref "T2") (pin "4") (pinfunction "S_4") (pintype "passive"))
      (node (ref "T5") (pin "4") (pinfunction "S_4") (pintype "passive"))
    )
    (net (code "4") (name "/BATTERY_MONITOR_0-1V") (class "Default")
      (node (ref "IC1") (pin "97") (pinfunction "PA2(ADCA2)_97") (pintype "bidirectional"))
      (node (ref "R60") (pin "1") (pinfunction "1_1") (pintype "bidirectional"))
      (node (ref "R61") (pin "2") (pinfunction "2_2") (pintype "bidirectional"))
    )
    (net (code "5") (name "/BEACON_ID_0_3V3") (class "Default")
      (node (ref "IC1") (pin "57") (pinfunction "PH2(~{RAS}/ALE1)_57") (pintype "bidirectional"))
      (node (ref "R1") (pin "2") (pinfunction "2_2") (pintype "bidirectional"))
    )
    (net (code "6") (name "/BEACON_ID_1_3V3") (class "Default")
      (node (ref "IC1") (pin "58") (pinfunction "PH3(~{DOM}/ALE2)_58") (pintype "bidirectional"))
      (node (ref "R2") (pin "2") (pinfunction "2_2") (pintype "bidirectional"))
    )
    (net (code "7") (name "/BEACON_ID_2_3V3") (class "Default")
      (node (ref "IC1") (pin "59") (pinfunction "PH4(BA0/~{CS0}/A16)_59") (pintype "bidirectional"))
      (node (ref "R4") (pin "2") (pinfunction "2_2") (pintype "bidirectional"))
    )
    (net (code "8") (name "/INT0_0_3V3") (class "Default")
      (node (ref "IC1") (pin "39") (pinfunction "PE4(OC1A/~{SS})_39") (pintype "bidirectional"))
      (node (ref "IC4") (pin "17") (pinfunction "IO_VL4_17") (pintype "bidirectional"))
      (node (ref "R50") (pin "1") (pinfunction "1_1") (pintype "bidirectional"))
    )
    (net (code "9") (name "/INT0_0_5V") (class "Default")
      (node (ref "BAL1") (pin "2") (pinfunction "2_2") (pintype "passive"))
      (node (ref "IC2") (pin "8") (pinfunction "IO_VCC5_8") (pintype "bidirectional"))
      (node (ref "R73") (pin "2") (pinfunction "2_2") (pintype "bidirectional"))
    )
    (net (code "10") (name "/INT0_1_3V3") (class "Default")
      (node (ref "IC1") (pin "40") (pinfunction "PE5(OC1B/XCK1/MOSI)_40") (pintype "bidirectional"))
      (node (ref "IC4") (pin "16") (pinfunction "IO_VL5_16") (pintype "bidirectional"))
      (node (ref "R45") (pin "1") (pinfunction "1_1") (pintype "bidirectional"))
    )
    (net (code "11") (name "/INT0_1_5V") (class "Default")
      (node (ref "BAL2") (pin "2") (pinfunction "2_2") (pintype "passive"))
      (node (ref "IC2") (pin "7") (pinfunction "IO_VCC4_7") (pintype "bidirectional"))
      (node (ref "R69") (pin "2") (pinfunction "2_2") (pintype "bidirectional"))
    )
    (net (code "12") (name "/INT1_0_3V3") (class "Default")
      (node (ref "IC1") (pin "41") (pinfunction "PE6(RSC1/MISO/TOSC2)_41") (pintype "bidirectional"))
      (node (ref "IC4") (pin "15") (pinfunction "IO_VL6_15") (pintype "bidirectional"))
      (node (ref "R49") (pin "1") (pinfunction "1_1") (pintype "bidirectional"))
    )
    (net (code "13") (name "/INT1_0_5V") (class "Default")
      (node (ref "BAL1") (pin "6") (pinfunction "6_6") (pintype "passive"))
      (node (ref "IC2") (pin "6") (pinfunction "IO_VCC3_6") (pintype "bidirectional"))
      (node (ref "R68") (pin "2") (pinfunction "2_2") (pintype "bidirectional"))
    )
    (net (code "14") (name "/INT1_1_3V3") (class "Default")
      (node (ref "IC1") (pin "42") (pinfunction "PE7(TSD1/SCK/CLKO/EVO/TOSC1)_42") (pintype "bidirectional"))
      (node (ref "IC4") (pin "14") (pinfunction "IO_VL7_14") (pintype "bidirectional"))
      (node (ref "R44") (pin "1") (pinfunction "1_1") (pintype "bidirectional"))
    )
    (net (code "15") (name "/INT1_1_5V") (class "Default")
      (node (ref "BAL2") (pin "6") (pinfunction "6_6") (pintype "passive"))
      (node (ref "IC2") (pin "5") (pinfunction "IO_VCC2_5") (pintype "bidirectional"))
      (node (ref "R70") (pin "2") (pinfunction "2_2") (pintype "bidirectional"))
    )
    (net (code "16") (name "/IR_SENSOR_0_OUTPUT_3V3") (class "Default")
      (node (ref "D3") (pin "C") (pinfunction "C_C") (pintype "passive"))
      (node (ref "IC1") (pin "30") (pinfunction "PD5(OC1B/XCK1/MOSI)_30") (pintype "bidirectional"))
      (node (ref "R29") (pin "2") (pinfunction "2_2") (pintype "bidirectional"))
      (node (ref "R36") (pin "2") (pinfunction "2_2") (pintype "bidirectional"))
      (node (ref "R74") (pin "1") (pinfunction "1_1") (pintype "bidirectional"))
    )
    (net (code "17") (name "/IR_SENSOR_0_OUTPUT_24V") (class "Default")
      (node (ref "IR_SENSOR1") (pin "2") (pinfunction "2_2") (pintype "passive"))
      (node (ref "R20") (pin "1") (pinfunction "1_1") (pintype "bidirectional"))
      (node (ref "R21") (pin "2") (pinfunction "2_2") (pintype "passive"))
      (node (ref "R34") (pin "1") (pinfunction "1_1") (pintype "bidirectional"))
    )
    (net (code "18") (name "/IR_SENSOR_1_OUTPUT_3V3") (class "Default")
      (node (ref "D4") (pin "C") (pinfunction "C_C") (pintype "passive"))
      (node (ref "IC1") (pin "15") (pinfunction "PC0(OC0A/SDA)_15") (pintype "bidirectional"))
      (node (ref "R34") (pin "2") (pinfunction "2_2") (pintype "bidirectional"))
      (node (ref "R41") (pin "2") (pinfunction "2_2") (pintype "bidirectional"))
      (node (ref "R75") (pin "1") (pinfunction "1_1") (pintype "bidirectional"))
    )
    (net (code "19") (name "/LED_INDEX_0_3V3") (class "Default")
      (node (ref "IC1") (pin "6") (pinfunction "PB1(ADCB1)_6") (pintype "bidirectional"))
      (node (ref "R57") (pin "1") (pinfunction "1_1") (pintype "bidirectional"))
    )
    (net (code "20") (name "/LED_INDEX_1_3V3") (class "Default")
      (node (ref "IC1") (pin "55") (pinfunction "PH0(~{WE})_55") (pintype "bidirectional"))
      (node (ref "R59") (pin "1") (pinfunction "1_1") (pintype "bidirectional"))
    )
    (net (code "21") (name "/LK0_3V3") (class "Default")
      (node (ref "IC1") (pin "7") (pinfunction "PB2(ADCB2/DAC0)_7") (pintype "bidirectional"))
      (node (ref "R47") (pin "1") (pinfunction "1_1") (pintype "bidirectional"))
    )
    (net (code "22") (name "/LK1_3V3") (class "Default")
      (node (ref "IC1") (pin "8") (pinfunction "PB3(ADCB3/DAC1)_8") (pintype "bidirectional"))
      (node (ref "R52") (pin "1") (pinfunction "1_1") (pintype "bidirectional"))
    )
    (net (code "23") (name "/LK2_3V3") (class "Default")
      (node (ref "IC1") (pin "9") (pinfunction "PB4(ADCB4/TMS)_9") (pintype "bidirectional"))
      (node (ref "R56") (pin "1") (pinfunction "1_1") (pintype "bidirectional"))
    )
    (net (code "24") (name "/LK3_3V3") (class "Default")
      (node (ref "IC1") (pin "10") (pinfunction "PB5(ADCB5/TDI)_10") (pintype "bidirectional"))
      (node (ref "R58") (pin "1") (pinfunction "1_1") (pintype "bidirectional"))
    )
    (net (code "25") (name "/LK4_3V3") (class "Default")
      (node (ref "IC1") (pin "11") (pinfunction "PB6(ADCB6/TCK)_11") (pintype "bidirectional"))
      (node (ref "R48") (pin "1") (pinfunction "1_1") (pintype "bidirectional"))
    )
    (net (code "26") (name "/LK5_3V3") (class "Default")
      (node (ref "IC1") (pin "12") (pinfunction "PB7(ADCB7/AC0-OUT/TDO)_12") (pintype "bidirectional"))
      (node (ref "R53") (pin "1") (pinfunction "1_1") (pintype "bidirectional"))
    )
    (net (code "27") (name "/LOW_BAT_LED_3V3") (class "Default")
      (node (ref "IC1") (pin "36") (pinfunction "PE1(OC0B/XCK0/SCL)_36") (pintype "bidirectional"))
      (node (ref "R40") (pin "1") (pinfunction "1_1") (pintype "bidirectional"))
    )
    (net (code "28") (name "/MIRROR_INDEX_0_3V3") (class "Default")
      (node (ref "IC1") (pin "29") (pinfunction "PD4(OC1A/~{SS})_29") (pintype "bidirectional"))
      (node (ref "IDX0") (pin "4") (pinfunction "IDX_3V3_4") (pintype "bidirectional"))
    )
    (net (code "29") (name "/MIRROR_INDEX_1_3V3") (class "Default")
      (node (ref "IC1") (pin "18") (pinfunction "PC3(OC0D/TXD0)_18") (pintype "bidirectional"))
      (node (ref "IC1") (pin "19") (pinfunction "PC4(OC1A/~{SS})_19") (pintype "bidirectional"))
      (node (ref "IDX1") (pin "TRANSISTOR_C") (pinfunction "TRANSISTOR_C_TRANSISTOR_C") (pintype "passive"))
      (node (ref "R24") (pin "1") (pinfunction "1_1") (pintype "bidirectional"))
    )
    (net (code "30") (name "/MOTOR_M_0") (class "Default")
      (node (ref "D2") (pin "A") (pinfunction "A_A") (pintype "passive"))
      (node (ref "MOT0") (pin "1") (pinfunction "S_1") (pintype "passive"))
      (node (ref "T6") (pin "C") (pinfunction "C_C") (pintype "passive"))
    )
    (net (code "31") (name "/MOTOR_M_1") (class "Default")
      (node (ref "D1") (pin "A") (pinfunction "A_A") (pintype "passive"))
      (node (ref "MOT1") (pin "1") (pinfunction "S_1") (pintype "passive"))
      (node (ref "T4") (pin "C") (pinfunction "C_C") (pintype "passive"))
    )
    (net (code "32") (name "/MOTOR_PWM_0_3V3") (class "Default")
      (node (ref "IC1") (pin "25") (pinfunction "PD0(OC0A/SDA)_25") (pintype "bidirectional"))
      (node (ref "R13") (pin "2") (pinfunction "2_2") (pintype "bidirectional"))
      (node (ref "R16") (pin "1") (pinfunction "1_1") (pintype "bidirectional"))
    )
    (net (code "33") (name "/MOTOR_PWM_1_3V3") (class "Default")
      (node (ref "IC1") (pin "26") (pinfunction "PD1(OC0B/XCK0/SCL)_26") (pintype "bidirectional"))
      (node (ref "R11") (pin "2") (pinfunction "2_2") (pintype "bidirectional"))
      (node (ref "R12") (pin "1") (pinfunction "1_1") (pintype "bidirectional"))
    )
    (net (code "34") (name "/NRF_CSN_3V3") (class "Default")
      (node (ref "IC1") (pin "2") (pinfunction "PA7/(ADCA7/AC0-OUT)_2") (pintype "bidirectional"))
      (node (ref "IC7") (pin "4") (pinfunction "CSN_4") (pintype "bidirectional"))
      (node (ref "R67") (pin "1") (pinfunction "1_1") (pintype "bidirectional"))
    )
    (net (code "35") (name "/NRF_MOSI_3V3") (class "Default")
      (node (ref "IC1") (pin "20") (pinfunction "PC5(OC1B/MOSI/XCK1)_20") (pintype "bidirectional"))
      (node (ref "IC7") (pin "6") (pinfunction "MOSI_6") (pintype "input"))
    )
    (net (code "36") (name "/ON{slash}OFF_SENSOR_0_3V3") (class "Default")
      (node (ref "IC1") (pin "32") (pinfunction "PD7(TXD1/SCK/CLKO/EVO)_32") (pintype "bidirectional"))
      (node (ref "R7") (pin "2") (pinfunction "2_2") (pintype "bidirectional"))
      (node (ref "R8") (pin "1") (pinfunction "1_1") (pintype "bidirectional"))
    )
    (net (code "37") (name "/ON{slash}OFF_SENSOR_1_3V3") (class "Default")
      (node (ref "IC1") (pin "17") (pinfunction "PC2(OC0C/RXD0)_17") (pintype "bidirectional"))
      (node (ref "R5") (pin "2") (pinfunction "2_2") (pintype "bidirectional"))
      (node (ref "R6") (pin "1") (pinfunction "1_1") (pintype "bidirectional"))
    )
    (net (code "38") (name "/PDI_DATA_3V3") (class "Default")
      (node (ref "IC1") (pin "89") (pinfunction "PDI-DATA_89") (pintype "bidirectional"))
      (node (ref "PDI_ATMEL") (pin "1") (pinfunction "DATA_1") (pintype "passive"))
    )
    (net (code "39") (name "/RX_0_3V3") (class "Default")
      (node (ref "IC1") (pin "47") (pinfunction "PF2(OC0C/RXD0)_47") (pintype "bidirectional"))
      (node (ref "IC8") (pin "12") (pinfunction "R1OUT_12") (pintype "output"))
      (node (ref "R30") (pin "2") (pinfunction "2_2") (pintype "bidirectional"))
    )
    (net (code "40") (name "/RX_0_RS232") (class "Default")
      (node (ref "BAL1") (pin "8") (pinfunction "8_8") (pintype "passive"))
      (node (ref "IC8") (pin "13") (pinfunction "R1IN_13") (pintype "input"))
    )
    (net (code "41") (name "/RX_1_3V3") (class "Default")
      (node (ref "IC1") (pin "51") (pinfunction "PF6(RXD1/MISO)_51") (pintype "bidirectional"))
      (node (ref "IC8") (pin "9") (pinfunction "R2OUT_9") (pintype "output"))
      (node (ref "R37") (pin "1") (pinfunction "1_1") (pintype "bidirectional"))
    )
    (net (code "42") (name "/RX_1_RS232") (class "Default")
      (node (ref "BAL2") (pin "8") (pinfunction "8_8") (pintype "passive"))
      (node (ref "IC8") (pin "8") (pinfunction "R2IN_8") (pintype "input"))
    )
    (net (code "43") (name "/SYNC1_LED_3V3") (class "Default")
      (node (ref "IC1") (pin "35") (pinfunction "PE0(OC0A/SDA)_35") (pintype "bidirectional"))
      (node (ref "R32") (pin "2") (pinfunction "2_2") (pintype "bidirectional"))
    )
    (net (code "44") (name "/SYNC_IN_0_3V3") (class "Default")
      (node (ref "IC1") (pin "37") (pinfunction "PE2(OC0C/RXD0)_37") (pintype "bidirectional"))
      (node (ref "IC2") (pin "15") (pinfunction "IO_VL6_15") (pintype "bidirectional"))
    )
    (net (code "45") (name "/SYNC_IN_0_5V") (class "Default")
      (node (ref "BAL1") (pin "7") (pinfunction "7_7") (pintype "passive"))
      (node (ref "IC2") (pin "9") (pinfunction "IO_VCC6_9") (pintype "bidirectional"))
    )
    (net (code "46") (name "/SYNC_IN_1_3V3") (class "Default")
      (node (ref "IC1") (pin "31") (pinfunction "PD6(RXD1/MISO)_31") (pintype "bidirectional"))
      (node (ref "IC2") (pin "14") (pinfunction "IO_VL7_14") (pintype "bidirectional"))
    )
    (net (code "47") (name "/SYNC_IN_1_5V") (class "Default")
      (node (ref "BAL2") (pin "7") (pinfunction "7_7") (pintype "passive"))
      (node (ref "IC2") (pin "10") (pinfunction "IO_VCC7_10") (pintype "bidirectional"))
    )
    (net (code "48") (name "/SYNC_OUT_0_3V3") (class "Default")
      (node (ref "IC1") (pin "50") (pinfunction "PF5(OC1B/XCK1/MOSI)_50") (pintype "bidirectional"))
      (node (ref "IC4") (pin "21") (pinfunction "IO_VL0_21") (pintype "bidirectional"))
    )
    (net (code "49") (name "/SYNC_OUT_0_5V") (class "Default")
      (node (ref "BAL1") (pin "3") (pinfunction "3_3") (pintype "passive"))
      (node (ref "IC4") (pin "3") (pinfunction "IO_VCC0_3") (pintype "bidirectional"))
    )
    (net (code "50") (name "/SYNC_OUT_1_3V3") (class "Default")
      (node (ref "IC1") (pin "49") (pinfunction "PF4(OC1A/~{SS})_49") (pintype "bidirectional"))
      (node (ref "IC4") (pin "20") (pinfunction "IO_VL1_20") (pintype "bidirectional"))
    )
    (net (code "51") (name "/SYNC_OUT_1_5V") (class "Default")
      (node (ref "BAL2") (pin "3") (pinfunction "3_3") (pintype "passive"))
      (node (ref "IC4") (pin "4") (pinfunction "IO_VCC1_4") (pintype "bidirectional"))
    )
    (net (code "52") (name "/TX_0_3V3") (class "Default")
      (node (ref "IC1") (pin "48") (pinfunction "PF3(OC0D/TXD0)_48") (pintype "bidirectional"))
      (node (ref "IC8") (pin "11") (pinfunction "T1IN_11") (pintype "input"))
      (node (ref "R33") (pin "2") (pinfunction "2_2") (pintype "bidirectional"))
    )
    (net (code "53") (name "/TX_0_RS232") (class "Default")
      (node (ref "BAL1") (pin "4") (pinfunction "4_4") (pintype "passive"))
      (node (ref "IC8") (pin "14") (pinfunction "T1OUT_14") (pintype "output"))
    )
    (net (code "54") (name "/TX_1_3V3") (class "Default")
      (node (ref "IC1") (pin "52") (pinfunction "PF7(TXD1/SCK)_52") (pintype "bidirectional"))
      (node (ref "IC8") (pin "10") (pinfunction "T2IN_10") (pintype "input"))
      (node (ref "R39") (pin "1") (pinfunction "1_1") (pintype "bidirectional"))
    )
    (net (code "55") (name "/TX_1_RS232") (class "Default")
      (node (ref "BAL2") (pin "4") (pinfunction "4_4") (pintype "passive"))
      (node (ref "IC8") (pin "7") (pinfunction "T2OUT_7") (pintype "output"))
    )
    (net (code "56") (name "/XBEE_CTS_3V3{slash}NRF_IRQ_3V3") (class "Default")
      (node (ref "IC1") (pin "16") (pinfunction "PC1(OC0B/XCK0/SCL)_16") (pintype "bidirectional"))
      (node (ref "IC7") (pin "8") (pinfunction "IRQ_8") (pintype "bidirectional"))
      (node (ref "XB1") (pin "12") (pinfunction "~{CTS}/DIO7_12") (pintype "bidirectional"))
    )
    (net (code "57") (name "/XBEE_RTS_3V3{slash}NRF_CE_3V3") (class "Default")
      (node (ref "IC1") (pin "5") (pinfunction "PB0(ADCB0/AREFB)_5") (pintype "bidirectional"))
      (node (ref "IC7") (pin "3") (pinfunction "CE_3") (pintype "bidirectional"))
      (node (ref "XB1") (pin "16") (pinfunction "~{RTS}/AD6/DIO6_16") (pintype "bidirectional"))
    )
    (net (code "58") (name "/XBEE_RX_3V3{slash}NRF_MISO_3V3") (class "Default")
      (node (ref "IC1") (pin "21") (pinfunction "PC6(MISO/RXD1)_21") (pintype "bidirectional"))
      (node (ref "IC7") (pin "7") (pinfunction "MISO_7") (pintype "bidirectional"))
      (node (ref "R43") (pin "2") (pinfunction "2_2") (pintype "bidirectional"))
      (node (ref "XB1") (pin "2") (pinfunction "DOUT_2") (pintype "output"))
    )
    (net (code "59") (name "/XBEE_TX_3V3{slash}NRF_SCK_3V3") (class "Default")
      (node (ref "IC1") (pin "22") (pinfunction "PC7(SCK/TXD1/CLKO/EVO)_22") (pintype "bidirectional"))
      (node (ref "IC7") (pin "5") (pinfunction "SCK_5") (pintype "bidirectional"))
      (node (ref "R42") (pin "2") (pinfunction "2_2") (pintype "bidirectional"))
      (node (ref "XB1") (pin "3") (pinfunction "DIN/~{CONFIG}_3") (pintype "input"))
    )
    (net (code "60") (name "/{slash}RESET_3V3") (class "Default")
      (node (ref "IC1") (pin "90") (pinfunction "PDI-CLK/~{RESET}_90") (pintype "input"))
      (node (ref "PDI_ATMEL") (pin "5") (pinfunction "CLK_5") (pintype "passive"))
      (node (ref "R3") (pin "2") (pinfunction "2_2") (pintype "bidirectional"))
    )
    (net (code "61") (name "GND") (class "Default")
      (node (ref "BAL1") (pin "1") (pinfunction "1_1") (pintype "passive"))
      (node (ref "BAL2") (pin "1") (pinfunction "1_1") (pintype "passive"))
      (node (ref "BATT") (pin "1") (pinfunction "1_1") (pintype "passive"))
      (node (ref "C1") (pin "2") (pinfunction "2_2") (pintype "passive"))
      (node (ref "C10") (pin "2") (pinfunction "2_2") (pintype "passive"))
      (node (ref "C11") (pin "2") (pinfunction "2_2") (pintype "passive"))
      (node (ref "C12") (pin "2") (pinfunction "2_2") (pintype "passive"))
      (node (ref "C13") (pin "2") (pinfunction "2_2") (pintype "passive"))
      (node (ref "C14") (pin "2") (pinfunction "2_2") (pintype "passive"))
      (node (ref "C15") (pin "2") (pinfunction "2_2") (pintype "passive"))
      (node (ref "C16") (pin "2") (pinfunction "2_2") (pintype "passive"))
      (node (ref "C17") (pin "2") (pinfunction "2_2") (pintype "passive"))
      (node (ref "C18") (pin "2") (pinfunction "2_2") (pintype "passive"))
      (node (ref "C19") (pin "2") (pinfunction "2_2") (pintype "passive"))
      (node (ref "C2") (pin "2") (pinfunction "2_2") (pintype "passive"))
      (node (ref "C20") (pin "2") (pinfunction "2_2") (pintype "passive"))
      (node (ref "C21") (pin "2") (pinfunction "2_2") (pintype "passive"))
      (node (ref "C22") (pin "2") (pinfunction "2_2") (pintype "passive"))
      (node (ref "C23") (pin "2") (pinfunction "2_2") (pintype "passive"))
      (node (ref "C24") (pin "-") (pinfunction "-_-") (pintype "passive"))
      (node (ref "C25") (pin "2") (pinfunction "2_2") (pintype "passive"))
      (node (ref "C26") (pin "2") (pinfunction "2_2") (pintype "passive"))
      (node (ref "C27") (pin "2") (pinfunction "2_2") (pintype "passive"))
      (node (ref "C28") (pin "2") (pinfunction "2_2") (pintype "passive"))
      (node (ref "C29") (pin "2") (pinfunction "2_2") (pintype "passive"))
      (node (ref "C3") (pin "2") (pinfunction "2_2") (pintype "passive"))
      (node (ref "C30") (pin "2") (pinfunction "2_2") (pintype "passive"))
      (node (ref "C31") (pin "2") (pinfunction "2_2") (pintype "passive"))
      (node (ref "C32") (pin "2") (pinfunction "2_2") (pintype "passive"))
      (node (ref "C33") (pin "2") (pinfunction "2_2") (pintype "passive"))
      (node (ref "C34") (pin "2") (pinfunction "2_2") (pintype "passive"))
      (node (ref "C35") (pin "2") (pinfunction "2_2") (pintype "passive"))
      (node (ref "C37") (pin "2") (pinfunction "2_2") (pintype "passive"))
      (node (ref "C38") (pin "2") (pinfunction "2_2") (pintype "passive"))
      (node (ref "C39") (pin "2") (pinfunction "2_2") (pintype "passive"))
      (node (ref "C4") (pin "2") (pinfunction "2_2") (pintype "passive"))
      (node (ref "C41") (pin "2") (pinfunction "2_2") (pintype "passive"))
      (node (ref "C43") (pin "2") (pinfunction "2_2") (pintype "passive"))
      (node (ref "C5") (pin "2") (pinfunction "2_2") (pintype "passive"))
      (node (ref "C6") (pin "2") (pinfunction "2_2") (pintype "passive"))
      (node (ref "C7") (pin "2") (pinfunction "2_2") (pintype "passive"))
      (node (ref "C8") (pin "2") (pinfunction "2_2") (pintype "passive"))
      (node (ref "C9") (pin "2") (pinfunction "2_2") (pintype "passive"))
      (node (ref "COM") (pin "C") (pinfunction "C_C") (pintype "passive"))
      (node (ref "D3") (pin "A") (pinfunction "A_A") (pintype "passive"))
      (node (ref "D4") (pin "A") (pinfunction "A_A") (pintype "passive"))
      (node (ref "ERROR") (pin "C") (pinfunction "C_C") (pintype "passive"))
      (node (ref "H1") (pin "B5,5") (pinfunction "MOUNT_B5,5") (pintype "passive"))
      (node (ref "H2") (pin "B5,5") (pinfunction "MOUNT_B5,5") (pintype "passive"))
      (node (ref "H3") (pin "B5,5") (pinfunction "MOUNT_B5,5") (pintype "passive"))
      (node (ref "IC1") (pin "13") (pinfunction "GND_13") (pintype "power_in"))
      (node (ref "IC1") (pin "23") (pinfunction "GND_23") (pintype "power_in"))
      (node (ref "IC1") (pin "3") (pinfunction "GND_3") (pintype "power_in"))
      (node (ref "IC1") (pin "33") (pinfunction "GND_33") (pintype "power_in"))
      (node (ref "IC1") (pin "43") (pinfunction "GND_43") (pintype "power_in"))
      (node (ref "IC1") (pin "53") (pinfunction "GND_53") (pintype "power_in"))
      (node (ref "IC1") (pin "63") (pinfunction "GND_63") (pintype "power_in"))
      (node (ref "IC1") (pin "73") (pinfunction "GND_73") (pintype "power_in"))
      (node (ref "IC1") (pin "84") (pinfunction "GND_84") (pintype "power_in"))
      (node (ref "IC1") (pin "93") (pinfunction "GND_93") (pintype "power_in"))
      (node (ref "IC2") (pin "11") (pinfunction "GND_11") (pintype "power_in"))
      (node (ref "IC2") (pin "12") (pinfunction "GND_12") (pintype "power_in"))
      (node (ref "IC2") (pin "13") (pinfunction "GND_13") (pintype "power_in"))
      (node (ref "IC2") (pin "22") (pinfunction "/OE_22") (pintype "bidirectional"))
      (node (ref "IC3") (pin "2") (pinfunction "GND_2") (pintype "bidirectional"))
      (node (ref "IC4") (pin "11") (pinfunction "GND_11") (pintype "power_in"))
      (node (ref "IC4") (pin "12") (pinfunction "GND_12") (pintype "power_in"))
      (node (ref "IC4") (pin "13") (pinfunction "GND_13") (pintype "power_in"))
      (node (ref "IC4") (pin "2") (pinfunction "DIR_H_TO_L_2") (pintype "bidirectional"))
      (node (ref "IC4") (pin "22") (pinfunction "/OE_22") (pintype "bidirectional"))
      (node (ref "IC5") (pin "5") (pinfunction "SGND_5") (pintype "power_in"))
      (node (ref "IC5") (pin "7") (pinfunction "CSG_7") (pintype "input"))
      (node (ref "IC5") (pin "THERMAL") (pinfunction "THERMAL_GND_THERMAL") (pintype "power_in"))
      (node (ref "IC6") (pin "4") (pinfunction "GND_4") (pintype "passive"))
      (node (ref "IC7") (pin "1") (pinfunction "GND_1") (pintype "input"))
      (node (ref "IC8") (pin "15") (pinfunction "GND_15") (pintype "power_in"))
      (node (ref "IDX0") (pin "1") (pinfunction "GND_1") (pintype "bidirectional"))
      (node (ref "IDX0") (pin "3") (pinfunction "GND_3") (pintype "bidirectional"))
      (node (ref "IDX1") (pin "LED_C") (pinfunction "LED_C_LED_C") (pintype "passive"))
      (node (ref "IDX1") (pin "TRANSISTOR_E") (pinfunction "TRANSISTOR_E_TRANSISTOR_E") (pintype "passive"))
      (node (ref "IR_SENS0") (pin "1") (pinfunction "1_1") (pintype "passive"))
      (node (ref "IR_SENSOR1") (pin "1") (pinfunction "1_1") (pintype "passive"))
      (node (ref "LIDX0") (pin "C") (pinfunction "C_C") (pintype "passive"))
      (node (ref "LIDX1") (pin "C") (pinfunction "C_C") (pintype "passive"))
      (node (ref "LK0") (pin "C") (pinfunction "C_C") (pintype "passive"))
      (node (ref "LK1") (pin "C") (pinfunction "C_C") (pintype "passive"))
      (node (ref "LK2") (pin "C") (pinfunction "C_C") (pintype "passive"))
      (node (ref "LK3") (pin "C") (pinfunction "C_C") (pintype "passive"))
      (node (ref "LK4") (pin "C") (pinfunction "C_C") (pintype "passive"))
      (node (ref "LK5") (pin "C") (pinfunction "C_C") (pintype "passive"))
      (node (ref "LOW_BATT") (pin "C") (pinfunction "C_C") (pintype "passive"))
      (node (ref "PDI_ATMEL") (pin "6") (pinfunction "GND_6") (pintype "passive"))
      (node (ref "R1") (pin "1") (pinfunction "1_1") (pintype "bidirectional"))
      (node (ref "R11") (pin "1") (pinfunction "1_1") (pintype "bidirectional"))
      (node (ref "R13") (pin "1") (pinfunction "1_1") (pintype "bidirectional"))
      (node (ref "R19") (pin "1") (pinfunction "1_1") (pintype "passive"))
      (node (ref "R2") (pin "1") (pinfunction "1_1") (pintype "bidirectional"))
      (node (ref "R21") (pin "1") (pinfunction "1_1") (pintype "passive"))
      (node (ref "R23") (pin "1") (pinfunction "1_1") (pintype "bidirectional"))
      (node (ref "R27") (pin "1") (pinfunction "1_1") (pintype "passive"))
      (node (ref "R36") (pin "1") (pinfunction "1_1") (pintype "bidirectional"))
      (node (ref "R4") (pin "1") (pinfunction "1_1") (pintype "bidirectional"))
      (node (ref "R41") (pin "1") (pinfunction "1_1") (pintype "bidirectional"))
      (node (ref "R42") (pin "1") (pinfunction "1_1") (pintype "bidirectional"))
      (node (ref "R43") (pin "1") (pinfunction "1_1") (pintype "bidirectional"))
      (node (ref "R46") (pin "1") (pinfunction "1_1") (pintype "bidirectional"))
      (node (ref "R5") (pin "1") (pinfunction "1_1") (pintype "bidirectional"))
      (node (ref "R61") (pin "1") (pinfunction "1_1") (pintype "bidirectional"))
      (node (ref "R64") (pin "1") (pinfunction "1_1") (pintype "bidirectional"))
      (node (ref "R66") (pin "1") (pinfunction "1_1") (pintype "bidirectional"))
      (node (ref "R7") (pin "1") (pinfunction "1_1") (pintype "bidirectional"))
      (node (ref "R72") (pin "2") (pinfunction "2_2") (pintype "bidirectional"))
      (node (ref "RF") (pin "C") (pinfunction "C_C") (pintype "passive"))
      (node (ref "RUN") (pin "C") (pinfunction "C_C") (pintype "passive"))
      (node (ref "SYNC1") (pin "C") (pinfunction "C_C") (pintype "passive"))
      (node (ref "SYNC2") (pin "C") (pinfunction "C_C") (pintype "passive"))
      (node (ref "T1") (pin "E") (pinfunction "E_E") (pintype "passive"))
      (node (ref "T3") (pin "E") (pinfunction "E_E") (pintype "passive"))
      (node (ref "T4") (pin "E") (pinfunction "E_E") (pintype "passive"))
      (node (ref "T6") (pin "E") (pinfunction "E_E") (pintype "passive"))
      (node (ref "T7") (pin "E") (pinfunction "E_E") (pintype "passive"))
      (node (ref "XB1") (pin "10") (pinfunction "GND_10") (pintype "power_in"))
    )
    (net (code "62") (name "Net-(COM-PadA)") (class "Default")
      (node (ref "COM") (pin "A") (pinfunction "A_A") (pintype "passive"))
      (node (ref "R35") (pin "2") (pinfunction "2_2") (pintype "bidirectional"))
    )
    (net (code "63") (name "Net-(D5-A1)") (class "Default")
      (node (ref "BATT") (pin "2") (pinfunction "2_2") (pintype "passive"))
      (node (ref "D5") (pin "1") (pinfunction "A1_1") (pintype "passive"))
      (node (ref "D5") (pin "3") (pinfunction "A2_3") (pintype "passive"))
      (node (ref "SW_BATT") (pin "2") (pinfunction "1_2") (pintype "bidirectional"))
    )
    (net (code "64") (name "Net-(D5-C)") (class "Default")
      (node (ref "D5") (pin "4") (pinfunction "C_4") (pintype "passive"))
      (node (ref "R54") (pin "2") (pinfunction "2_2") (pintype "bidirectional"))
      (node (ref "T8") (pin "4") (pinfunction "S_4") (pintype "passive"))
    )
    (net (code "65") (name "Net-(ERROR-PadA)") (class "Default")
      (node (ref "ERROR") (pin "A") (pinfunction "A_A") (pintype "passive"))
      (node (ref "R31") (pin "2") (pinfunction "2_2") (pintype "bidirectional"))
    )
    (net (code "66") (name "Net-(IC1-AVCC-A)") (class "Default")
      (node (ref "C10") (pin "1") (pinfunction "1_1") (pintype "passive"))
      (node (ref "C15") (pin "1") (pinfunction "1_1") (pintype "passive"))
      (node (ref "IC1") (pin "4") (pinfunction "AVCC-B_4") (pintype "power_in"))
      (node (ref "IC1") (pin "94") (pinfunction "AVCC-A_94") (pintype "power_in"))
      (node (ref "L1") (pin "1") (pinfunction "1_1") (pintype "passive"))
    )
    (net (code "67") (name "Net-(IC1-PA6(ADCA6))") (class "Default")
      (node (ref "IC1") (pin "1") (pinfunction "PA6(ADCA6)_1") (pintype "bidirectional"))
      (node (ref "R28") (pin "1") (pinfunction "1_1") (pintype "bidirectional"))
    )
    (net (code "68") (name "Net-(IC1-PH1(~{CAS}{slash}~{RE}))") (class "Default")
      (node (ref "IC1") (pin "56") (pinfunction "PH1(~{CAS}/~{RE})_56") (pintype "bidirectional"))
      (node (ref "R38") (pin "2") (pinfunction "2_2") (pintype "bidirectional"))
    )
    (net (code "69") (name "Net-(IC1-PH5(BA1{slash}~{CS1}{slash}A17))") (class "Default")
      (node (ref "IC1") (pin "60") (pinfunction "PH5(BA1/~{CS1}/A17)_60") (pintype "bidirectional"))
      (node (ref "R31") (pin "1") (pinfunction "1_1") (pintype "bidirectional"))
    )
    (net (code "70") (name "Net-(IC1-PH6(CKE{slash}~{CS2}{slash}A18))") (class "Default")
      (node (ref "IC1") (pin "61") (pinfunction "PH6(CKE/~{CS2}/A18)_61") (pintype "bidirectional"))
      (node (ref "R25") (pin "1") (pinfunction "1_1") (pintype "bidirectional"))
    )
    (net (code "71") (name "Net-(IC1-PH7(CLK{slash}~{CS3}{slash}A19))") (class "Default")
      (node (ref "IC1") (pin "62") (pinfunction "PH7(CLK/~{CS3}/A19)_62") (pintype "bidirectional"))
      (node (ref "R35") (pin "1") (pinfunction "1_1") (pintype "bidirectional"))
    )
    (net (code "72") (name "Net-(IC1-PR0(XTAL2))") (class "Default")
      (node (ref "C1") (pin "1") (pinfunction "1_1") (pintype "passive"))
      (node (ref "IC1") (pin "91") (pinfunction "PR0(XTAL2)_91") (pintype "bidirectional"))
      (node (ref "Q1") (pin "1") (pinfunction "1_1") (pintype "passive"))
    )
    (net (code "73") (name "Net-(IC1-PR1(XTAL1))") (class "Default")
      (node (ref "C2") (pin "1") (pinfunction "1_1") (pintype "passive"))
      (node (ref "IC1") (pin "92") (pinfunction "PR1(XTAL1)_92") (pintype "bidirectional"))
      (node (ref "Q1") (pin "2") (pinfunction "2_2") (pintype "passive"))
    )
    (net (code "74") (name "Net-(IC2-IO_VL2)") (class "Default")
      (node (ref "IC2") (pin "19") (pinfunction "IO_VL2_19") (pintype "bidirectional"))
      (node (ref "R44") (pin "2") (pinfunction "2_2") (pintype "bidirectional"))
    )
    (net (code "75") (name "Net-(IC2-IO_VL3)") (class "Default")
      (node (ref "IC2") (pin "18") (pinfunction "IO_VL3_18") (pintype "bidirectional"))
      (node (ref "R49") (pin "2") (pinfunction "2_2") (pintype "bidirectional"))
    )
    (net (code "76") (name "Net-(IC2-IO_VL4)") (class "Default")
      (node (ref "IC2") (pin "17") (pinfunction "IO_VL4_17") (pintype "bidirectional"))
      (node (ref "R45") (pin "2") (pinfunction "2_2") (pintype "bidirectional"))
    )
    (net (code "77") (name "Net-(IC2-IO_VL5)") (class "Default")
      (node (ref "IC2") (pin "16") (pinfunction "IO_VL5_16") (pintype "bidirectional"))
      (node (ref "R50") (pin "2") (pinfunction "2_2") (pintype "bidirectional"))
    )
    (net (code "78") (name "Net-(IC3-FB)") (class "Default")
      (node (ref "C40") (pin "2") (pinfunction "2_2") (pintype "passive"))
      (node (ref "IC3") (pin "3") (pinfunction "FB_3") (pintype "bidirectional"))
      (node (ref "R65") (pin "2") (pinfunction "2_2") (pintype "bidirectional"))
      (node (ref "R66") (pin "2") (pinfunction "2_2") (pintype "bidirectional"))
    )
    (net (code "79") (name "Net-(IC3-SW)") (class "Default")
      (node (ref "D6") (pin "A") (pinfunction "A_A") (pintype "passive"))
      (node (ref "IC3") (pin "1") (pinfunction "SW_1") (pintype "bidirectional"))
      (node (ref "L2") (pin "2") (pinfunction "2_2") (pintype "passive"))
    )
    (net (code "80") (name "Net-(IC3-{slash}SHDN)") (class "Default")
      (node (ref "IC3") (pin "4") (pinfunction "/SHDN_4") (pintype "bidirectional"))
      (node (ref "R62") (pin "1") (pinfunction "1_1") (pintype "bidirectional"))
    )
    (net (code "81") (name "Net-(IC4-IO_VCC4)") (class "Default")
      (node (ref "IC4") (pin "7") (pinfunction "IO_VCC4_7") (pintype "bidirectional"))
      (node (ref "R73") (pin "1") (pinfunction "1_1") (pintype "bidirectional"))
    )
    (net (code "82") (name "Net-(IC4-IO_VCC5)") (class "Default")
      (node (ref "IC4") (pin "8") (pinfunction "IO_VCC5_8") (pintype "bidirectional"))
      (node (ref "R69") (pin "1") (pinfunction "1_1") (pintype "bidirectional"))
    )
    (net (code "83") (name "Net-(IC4-IO_VCC6)") (class "Default")
      (node (ref "IC4") (pin "9") (pinfunction "IO_VCC6_9") (pintype "bidirectional"))
      (node (ref "R68") (pin "1") (pinfunction "1_1") (pintype "bidirectional"))
    )
    (net (code "84") (name "Net-(IC4-IO_VCC7)") (class "Default")
      (node (ref "IC4") (pin "10") (pinfunction "IO_VCC7_10") (pintype "bidirectional"))
      (node (ref "R70") (pin "1") (pinfunction "1_1") (pintype "bidirectional"))
    )
    (net (code "85") (name "Net-(IC5-BST)") (class "Default")
      (node (ref "C36") (pin "1") (pinfunction "1_1") (pintype "passive"))
      (node (ref "IC5") (pin "10") (pinfunction "BST_10") (pintype "input"))
    )
    (net (code "86") (name "Net-(IC5-CS)") (class "Default")
      (node (ref "D7") (pin "A") (pinfunction "A_A") (pintype "passive"))
      (node (ref "IC5") (pin "8") (pinfunction "CS_8") (pintype "output"))
      (node (ref "R64") (pin "2") (pinfunction "2_2") (pintype "bidirectional"))
    )
    (net (code "87") (name "Net-(IC5-FB)") (class "Default")
      (node (ref "IC5") (pin "6") (pinfunction "FB_6") (pintype "input"))
      (node (ref "R71") (pin "2") (pinfunction "2_2") (pintype "bidirectional"))
      (node (ref "R72") (pin "1") (pinfunction "1_1") (pintype "bidirectional"))
    )
    (net (code "88") (name "Net-(IC5-RT)") (class "Default")
      (node (ref "IC5") (pin "2") (pinfunction "RT_2") (pintype "input"))
      (node (ref "R63") (pin "1") (pinfunction "1_1") (pintype "bidirectional"))
    )
    (net (code "89") (name "Net-(IC5-SS)") (class "Default")
      (node (ref "C33") (pin "1") (pinfunction "1_1") (pintype "passive"))
      (node (ref "IC5") (pin "4") (pinfunction "SS_4") (pintype "power_in"))
    )
    (net (code "90") (name "Net-(IC5-SW)") (class "Default")
      (node (ref "C36") (pin "2") (pinfunction "2_2") (pintype "passive"))
      (node (ref "D7") (pin "C") (pinfunction "C_C") (pintype "passive"))
      (node (ref "IC5") (pin "9") (pinfunction "SW_9") (pintype "output"))
      (node (ref "L3") (pin "1") (pinfunction "1_1") (pintype "passive"))
    )
    (net (code "91") (name "Net-(IC8A-C1+)") (class "Default")
      (node (ref "C44") (pin "1") (pinfunction "1_1") (pintype "passive"))
      (node (ref "IC8") (pin "1") (pinfunction "C1+_1") (pintype "bidirectional"))
    )
    (net (code "92") (name "Net-(IC8A-C1-)") (class "Default")
      (node (ref "C44") (pin "2") (pinfunction "2_2") (pintype "passive"))
      (node (ref "IC8") (pin "3") (pinfunction "C1-_3") (pintype "bidirectional"))
    )
    (net (code "93") (name "Net-(IC8A-C2+)") (class "Default")
      (node (ref "C42") (pin "1") (pinfunction "1_1") (pintype "passive"))
      (node (ref "IC8") (pin "4") (pinfunction "C2+_4") (pintype "bidirectional"))
    )
    (net (code "94") (name "Net-(IC8A-C2-)") (class "Default")
      (node (ref "C42") (pin "2") (pinfunction "2_2") (pintype "passive"))
      (node (ref "IC8") (pin "5") (pinfunction "C2-_5") (pintype "bidirectional"))
    )
    (net (code "95") (name "Net-(IC8A-V+)") (class "Default")
      (node (ref "C34") (pin "1") (pinfunction "1_1") (pintype "passive"))
      (node (ref "IC8") (pin "2") (pinfunction "V+_2") (pintype "bidirectional"))
    )
    (net (code "96") (name "Net-(IC8A-V-)") (class "Default")
      (node (ref "C35") (pin "1") (pinfunction "1_1") (pintype "passive"))
      (node (ref "IC8") (pin "6") (pinfunction "V-_6") (pintype "bidirectional"))
    )
    (net (code "97") (name "Net-(IDX1-PadLED_A)") (class "Default")
      (node (ref "IDX1") (pin "LED_A") (pinfunction "LED_A_LED_A") (pintype "passive"))
      (node (ref "R17") (pin "1") (pinfunction "1_1") (pintype "bidirectional"))
    )
    (net (code "98") (name "Net-(IR_SENS0-Pad2)") (class "Default")
      (node (ref "IR_SENS0") (pin "2") (pinfunction "2_2") (pintype "passive"))
      (node (ref "R26") (pin "1") (pinfunction "1_1") (pintype "bidirectional"))
      (node (ref "R27") (pin "2") (pinfunction "2_2") (pintype "passive"))
      (node (ref "R29") (pin "1") (pinfunction "1_1") (pintype "bidirectional"))
    )
    (net (code "99") (name "Net-(IR_SENS0-Pad3)") (class "Default")
      (node (ref "IR_SENS0") (pin "3") (pinfunction "3_3") (pintype "passive"))
      (node (ref "R22") (pin "2") (pinfunction "2_2") (pintype "bidirectional"))
      (node (ref "R26") (pin "2") (pinfunction "2_2") (pintype "bidirectional"))
      (node (ref "T5") (pin "1") (pinfunction "D_1") (pintype "passive"))
      (node (ref "T5") (pin "2") (pinfunction "D_2") (pintype "passive"))
      (node (ref "T5") (pin "5") (pinfunction "D_5") (pintype "passive"))
      (node (ref "T5") (pin "6") (pinfunction "D_6") (pintype "passive"))
    )
    (net (code "100") (name "Net-(IR_SENS0-Pad4)") (class "Default")
      (node (ref "IR_SENS0") (pin "4") (pinfunction "4_4") (pintype "passive"))
      (node (ref "R22") (pin "1") (pinfunction "1_1") (pintype "bidirectional"))
      (node (ref "R23") (pin "2") (pinfunction "2_2") (pintype "bidirectional"))
    )
    (net (code "101") (name "Net-(IR_SENSOR1-Pad3)") (class "Default")
      (node (ref "IR_SENSOR1") (pin "3") (pinfunction "3_3") (pintype "passive"))
      (node (ref "R18") (pin "2") (pinfunction "2_2") (pintype "passive"))
      (node (ref "R20") (pin "2") (pinfunction "2_2") (pintype "bidirectional"))
      (node (ref "T2") (pin "1") (pinfunction "D_1") (pintype "passive"))
      (node (ref "T2") (pin "2") (pinfunction "D_2") (pintype "passive"))
      (node (ref "T2") (pin "5") (pinfunction "D_5") (pintype "passive"))
      (node (ref "T2") (pin "6") (pinfunction "D_6") (pintype "passive"))
    )
    (net (code "102") (name "Net-(IR_SENSOR1-Pad4)") (class "Default")
      (node (ref "IR_SENSOR1") (pin "4") (pinfunction "4_4") (pintype "passive"))
      (node (ref "R18") (pin "1") (pinfunction "1_1") (pintype "passive"))
      (node (ref "R19") (pin "2") (pinfunction "2_2") (pintype "passive"))
    )
    (net (code "103") (name "Net-(LIDX0-PadA)") (class "Default")
      (node (ref "LIDX0") (pin "A") (pinfunction "A_A") (pintype "passive"))
      (node (ref "R57") (pin "2") (pinfunction "2_2") (pintype "bidirectional"))
    )
    (net (code "104") (name "Net-(LIDX1-PadA)") (class "Default")
      (node (ref "LIDX1") (pin "A") (pinfunction "A_A") (pintype "passive"))
      (node (ref "R59") (pin "2") (pinfunction "2_2") (pintype "bidirectional"))
    )
    (net (code "105") (name "Net-(LK0-PadA)") (class "Default")
      (node (ref "LK0") (pin "A") (pinfunction "A_A") (pintype "passive"))
      (node (ref "R47") (pin "2") (pinfunction "2_2") (pintype "bidirectional"))
    )
    (net (code "106") (name "Net-(LK1-PadA)") (class "Default")
      (node (ref "LK1") (pin "A") (pinfunction "A_A") (pintype "passive"))
      (node (ref "R52") (pin "2") (pinfunction "2_2") (pintype "bidirectional"))
    )
    (net (code "107") (name "Net-(LK2-PadA)") (class "Default")
      (node (ref "LK2") (pin "A") (pinfunction "A_A") (pintype "passive"))
      (node (ref "R56") (pin "2") (pinfunction "2_2") (pintype "bidirectional"))
    )
    (net (code "108") (name "Net-(LK3-PadA)") (class "Default")
      (node (ref "LK3") (pin "A") (pinfunction "A_A") (pintype "passive"))
      (node (ref "R58") (pin "2") (pinfunction "2_2") (pintype "bidirectional"))
    )
    (net (code "109") (name "Net-(LK4-PadA)") (class "Default")
      (node (ref "LK4") (pin "A") (pinfunction "A_A") (pintype "passive"))
      (node (ref "R48") (pin "2") (pinfunction "2_2") (pintype "bidirectional"))
    )
    (net (code "110") (name "Net-(LK5-PadA)") (class "Default")
      (node (ref "LK5") (pin "A") (pinfunction "A_A") (pintype "passive"))
      (node (ref "R53") (pin "2") (pinfunction "2_2") (pintype "bidirectional"))
    )
    (net (code "111") (name "Net-(LOW_BATT-PadA)") (class "Default")
      (node (ref "LOW_BATT") (pin "A") (pinfunction "A_A") (pintype "passive"))
      (node (ref "R40") (pin "2") (pinfunction "2_2") (pintype "bidirectional"))
    )
    (net (code "112") (name "Net-(MOT0B-S)") (class "Default")
      (node (ref "C7") (pin "1") (pinfunction "1_1") (pintype "passive"))
      (node (ref "D2") (pin "C") (pinfunction "C_C") (pintype "passive"))
      (node (ref "MOT0") (pin "2") (pinfunction "S_2") (pintype "passive"))
      (node (ref "R76") (pin "2") (pinfunction "2_2") (pintype "bidirectional"))
      (node (ref "R77") (pin "2") (pinfunction "2_2") (pintype "bidirectional"))
    )
    (net (code "113") (name "Net-(MOT1B-S)") (class "Default")
      (node (ref "C6") (pin "1") (pinfunction "1_1") (pintype "passive"))
      (node (ref "D1") (pin "C") (pinfunction "C_C") (pintype "passive"))
      (node (ref "MOT1") (pin "2") (pinfunction "S_2") (pintype "passive"))
      (node (ref "R78") (pin "2") (pinfunction "2_2") (pintype "bidirectional"))
      (node (ref "R79") (pin "2") (pinfunction "2_2") (pintype "bidirectional"))
    )
    (net (code "114") (name "Net-(R6-Pad2)") (class "Default")
      (node (ref "R6") (pin "2") (pinfunction "2_2") (pintype "bidirectional"))
      (node (ref "T1") (pin "B") (pinfunction "B_B") (pintype "passive"))
    )
    (net (code "115") (name "Net-(R8-Pad2)") (class "Default")
      (node (ref "R8") (pin "2") (pinfunction "2_2") (pintype "bidirectional"))
      (node (ref "T3") (pin "B") (pinfunction "B_B") (pintype "passive"))
    )
    (net (code "116") (name "Net-(R10-Pad1)") (class "Default")
      (node (ref "R10") (pin "1") (pinfunction "1_1") (pintype "bidirectional"))
      (node (ref "T1") (pin "C") (pinfunction "C_C") (pintype "passive"))
    )
    (net (code "117") (name "Net-(R12-Pad2)") (class "Default")
      (node (ref "R12") (pin "2") (pinfunction "2_2") (pintype "bidirectional"))
      (node (ref "T4") (pin "B") (pinfunction "B_B") (pintype "passive"))
    )
    (net (code "118") (name "Net-(R15-Pad1)") (class "Default")
      (node (ref "R15") (pin "1") (pinfunction "1_1") (pintype "bidirectional"))
      (node (ref "T3") (pin "C") (pinfunction "C_C") (pintype "passive"))
    )
    (net (code "119") (name "Net-(R16-Pad2)") (class "Default")
      (node (ref "R16") (pin "2") (pinfunction "2_2") (pintype "bidirectional"))
      (node (ref "T6") (pin "B") (pinfunction "B_B") (pintype "passive"))
    )
    (net (code "120") (name "Net-(R25-Pad2)") (class "Default")
      (node (ref "R25") (pin "2") (pinfunction "2_2") (pintype "bidirectional"))
      (node (ref "RUN") (pin "A") (pinfunction "A_A") (pintype "passive"))
    )
    (net (code "121") (name "Net-(R28-Pad2)") (class "Default")
      (node (ref "R28") (pin "2") (pinfunction "2_2") (pintype "bidirectional"))
      (node (ref "RF") (pin "A") (pinfunction "A_A") (pintype "passive"))
    )
    (net (code "122") (name "Net-(R32-Pad1)") (class "Default")
      (node (ref "R32") (pin "1") (pinfunction "1_1") (pintype "bidirectional"))
      (node (ref "SYNC1") (pin "A") (pinfunction "A_A") (pintype "passive"))
    )
    (net (code "123") (name "Net-(R38-Pad1)") (class "Default")
      (node (ref "R38") (pin "1") (pinfunction "1_1") (pintype "bidirectional"))
      (node (ref "SYNC2") (pin "A") (pinfunction "A_A") (pintype "passive"))
    )
    (net (code "124") (name "Net-(R46-Pad2)") (class "Default")
      (node (ref "R46") (pin "2") (pinfunction "2_2") (pintype "bidirectional"))
      (node (ref "R51") (pin "1") (pinfunction "1_1") (pintype "bidirectional"))
      (node (ref "SW_BATT") (pin "3") (pinfunction "3_3") (pintype "bidirectional"))
    )
    (net (code "125") (name "Net-(R51-Pad2)") (class "Default")
      (node (ref "R51") (pin "2") (pinfunction "2_2") (pintype "bidirectional"))
      (node (ref "T7") (pin "B") (pinfunction "B_B") (pintype "passive"))
    )
    (net (code "126") (name "Net-(R55-Pad1)") (class "Default")
      (node (ref "R55") (pin "1") (pinfunction "1_1") (pintype "bidirectional"))
      (node (ref "T7") (pin "C") (pinfunction "C_C") (pintype "passive"))
    )
    (net (code "127") (name "Net-(T2-G)") (class "Default")
      (node (ref "R10") (pin "2") (pinfunction "2_2") (pintype "bidirectional"))
      (node (ref "R9") (pin "1") (pinfunction "1_1") (pintype "bidirectional"))
      (node (ref "T2") (pin "3") (pinfunction "G_3") (pintype "passive"))
    )
    (net (code "128") (name "Net-(T5-G)") (class "Default")
      (node (ref "R14") (pin "1") (pinfunction "1_1") (pintype "bidirectional"))
      (node (ref "R15") (pin "2") (pinfunction "2_2") (pintype "bidirectional"))
      (node (ref "T5") (pin "3") (pinfunction "G_3") (pintype "passive"))
    )
    (net (code "129") (name "Net-(T8-G)") (class "Default")
      (node (ref "R54") (pin "1") (pinfunction "1_1") (pintype "bidirectional"))
      (node (ref "R55") (pin "2") (pinfunction "2_2") (pintype "bidirectional"))
      (node (ref "T8") (pin "3") (pinfunction "G_3") (pintype "passive"))
    )
    (net (code "130") (name "Vbat") (class "Default")
      (node (ref "BAL1") (pin "5") (pinfunction "5_5") (pintype "passive"))
      (node (ref "BAL2") (pin "5") (pinfunction "5_5") (pintype "passive"))
      (node (ref "C24") (pin "+") (pinfunction "+_+") (pintype "passive"))
      (node (ref "C26") (pin "1") (pinfunction "1_1") (pintype "passive"))
      (node (ref "C28") (pin "1") (pinfunction "1_1") (pintype "passive"))
      (node (ref "C29") (pin "1") (pinfunction "1_1") (pintype "passive"))
      (node (ref "C32") (pin "1") (pinfunction "1_1") (pintype "passive"))
      (node (ref "IC3") (pin "5") (pinfunction "VIN_5") (pintype "bidirectional"))
      (node (ref "IC5") (pin "1") (pinfunction "VIN_1") (pintype "input"))
      (node (ref "IC6") (pin "1") (pinfunction "VI_1") (pintype "input"))
      (node (ref "L2") (pin "1") (pinfunction "1_1") (pintype "passive"))
      (node (ref "R60") (pin "2") (pinfunction "2_2") (pintype "bidirectional"))
      (node (ref "R62") (pin "2") (pinfunction "2_2") (pintype "bidirectional"))
      (node (ref "R63") (pin "2") (pinfunction "2_2") (pintype "bidirectional"))
      (node (ref "R76") (pin "1") (pinfunction "1_1") (pintype "bidirectional"))
      (node (ref "R79") (pin "1") (pinfunction "1_1") (pintype "bidirectional"))
      (node (ref "T8") (pin "1") (pinfunction "D_1") (pintype "passive"))
      (node (ref "T8") (pin "2") (pinfunction "D_2") (pintype "passive"))
      (node (ref "T8") (pin "5") (pinfunction "D_5") (pintype "passive"))
      (node (ref "T8") (pin "6") (pinfunction "D_6") (pintype "passive"))
    )
    (net (code "131") (name "unconnected-(IC1-PA0(ADCA0{slash}AREFA)-Pad95)") (class "Default")
      (node (ref "IC1") (pin "95") (pinfunction "PA0(ADCA0/AREFA)_95") (pintype "bidirectional"))
    )
    (net (code "132") (name "unconnected-(IC1-PA1(ADCA1)-Pad96)") (class "Default")
      (node (ref "IC1") (pin "96") (pinfunction "PA1(ADCA1)_96") (pintype "bidirectional"))
    )
    (net (code "133") (name "unconnected-(IC1-PA3(ADCA3)-Pad98)") (class "Default")
      (node (ref "IC1") (pin "98") (pinfunction "PA3(ADCA3)_98") (pintype "bidirectional"))
    )
    (net (code "134") (name "unconnected-(IC1-PA4(ADCA4)-Pad99)") (class "Default")
      (node (ref "IC1") (pin "99") (pinfunction "PA4(ADCA4)_99") (pintype "bidirectional"))
    )
    (net (code "135") (name "unconnected-(IC1-PA5(ADCA5)-Pad100)") (class "Default")
      (node (ref "IC1") (pin "100") (pinfunction "PA5(ADCA5)_100") (pintype "bidirectional"))
    )
    (net (code "136") (name "unconnected-(IC1-PD2(OC0C{slash}RXD0)-Pad27)") (class "Default")
      (node (ref "IC1") (pin "27") (pinfunction "PD2(OC0C/RXD0)_27") (pintype "bidirectional"))
    )
    (net (code "137") (name "unconnected-(IC1-PD3(OC0D{slash}TXD0)-Pad28)") (class "Default")
      (node (ref "IC1") (pin "28") (pinfunction "PD3(OC0D/TXD0)_28") (pintype "bidirectional"))
    )
    (net (code "138") (name "unconnected-(IC1-PE3(OC0D{slash}TXD0)-Pad38)") (class "Default")
      (node (ref "IC1") (pin "38") (pinfunction "PE3(OC0D/TXD0)_38") (pintype "bidirectional"))
    )
    (net (code "139") (name "unconnected-(IC1-PF0(OC0A{slash}SDA)-Pad45)") (class "Default")
      (node (ref "IC1") (pin "45") (pinfunction "PF0(OC0A/SDA)_45") (pintype "bidirectional"))
    )
    (net (code "140") (name "unconnected-(IC1-PF1(OC0B{slash}XCK0{slash}SCL)-Pad46)") (class "Default")
      (node (ref "IC1") (pin "46") (pinfunction "PF1(OC0B/XCK0/SCL)_46") (pintype "bidirectional"))
    )
    (net (code "141") (name "unconnected-(IC1-PJ0(D0{slash}A0{slash}A8)-Pad65)") (class "Default")
      (node (ref "IC1") (pin "65") (pinfunction "PJ0(D0/A0/A8)_65") (pintype "bidirectional"))
    )
    (net (code "142") (name "unconnected-(IC1-PJ1(D1{slash}A1{slash}A9)-Pad66)") (class "Default")
      (node (ref "IC1") (pin "66") (pinfunction "PJ1(D1/A1/A9)_66") (pintype "bidirectional"))
    )
    (net (code "143") (name "unconnected-(IC1-PJ2(D2{slash}A2{slash}A10)-Pad67)") (class "Default")
      (node (ref "IC1") (pin "67") (pinfunction "PJ2(D2/A2/A10)_67") (pintype "bidirectional"))
    )
    (net (code "144") (name "unconnected-(IC1-PJ3(D3{slash}A3{slash}A11)-Pad68)") (class "Default")
      (node (ref "IC1") (pin "68") (pinfunction "PJ3(D3/A3/A11)_68") (pintype "bidirectional"))
    )
    (net (code "145") (name "unconnected-(IC1-PJ4(A8{slash}D4{slash}A4{slash}A12)-Pad69)") (class "Default")
      (node (ref "IC1") (pin "69") (pinfunction "PJ4(A8/D4/A4/A12)_69") (pintype "bidirectional"))
    )
    (net (code "146") (name "unconnected-(IC1-PJ5(A9{slash}D5{slash}A5{slash}A13)-Pad70)") (class "Default")
      (node (ref "IC1") (pin "70") (pinfunction "PJ5(A9/D5/A5/A13)_70") (pintype "bidirectional"))
    )
    (net (code "147") (name "unconnected-(IC1-PJ6(A10{slash}D6{slash}A6{slash}A14)-Pad71)") (class "Default")
      (node (ref "IC1") (pin "71") (pinfunction "PJ6(A10/D6/A6/A14)_71") (pintype "bidirectional"))
    )
    (net (code "148") (name "unconnected-(IC1-PJ7(A11{slash}D7{slash}A7{slash}A15)-Pad72)") (class "Default")
      (node (ref "IC1") (pin "72") (pinfunction "PJ7(A11/D7/A7/A15)_72") (pintype "bidirectional"))
    )
    (net (code "149") (name "unconnected-(IC1-PK0(A0{slash}A8{slash}A16)-Pad75)") (class "Default")
      (node (ref "IC1") (pin "75") (pinfunction "PK0(A0/A8/A16)_75") (pintype "bidirectional"))
    )
    (net (code "150") (name "unconnected-(IC1-PK1(A1{slash}A9{slash}A17)-Pad76)") (class "Default")
      (node (ref "IC1") (pin "76") (pinfunction "PK1(A1/A9/A17)_76") (pintype "bidirectional"))
    )
    (net (code "151") (name "unconnected-(IC1-PK2(A2{slash}A10{slash}A18)-Pad77)") (class "Default")
      (node (ref "IC1") (pin "77") (pinfunction "PK2(A2/A10/A18)_77") (pintype "bidirectional"))
    )
    (net (code "152") (name "unconnected-(IC1-PK3(A3{slash}A11{slash}A19)-Pad78)") (class "Default")
      (node (ref "IC1") (pin "78") (pinfunction "PK3(A3/A11/A19)_78") (pintype "bidirectional"))
    )
    (net (code "153") (name "unconnected-(IC1-PK4(A4{slash}A12{slash}A20)-Pad79)") (class "Default")
      (node (ref "IC1") (pin "79") (pinfunction "PK4(A4/A12/A20)_79") (pintype "bidirectional"))
    )
    (net (code "154") (name "unconnected-(IC1-PK5(A5{slash}A13{slash}A22)-Pad80)") (class "Default")
      (node (ref "IC1") (pin "80") (pinfunction "PK5(A5/A13/A22)_80") (pintype "bidirectional"))
    )
    (net (code "155") (name "unconnected-(IC1-PK6(A6{slash}A14{slash}A22)-Pad81)") (class "Default")
      (node (ref "IC1") (pin "81") (pinfunction "PK6(A6/A14/A22)_81") (pintype "bidirectional"))
    )
    (net (code "156") (name "unconnected-(IC1-PK7(A7{slash}A15{slash}A23)-Pad82)") (class "Default")
      (node (ref "IC1") (pin "82") (pinfunction "PK7(A7/A15/A23)_82") (pintype "bidirectional"))
    )
    (net (code "157") (name "unconnected-(IC1-PQ0(TOSC1)-Pad85)") (class "Default")
      (node (ref "IC1") (pin "85") (pinfunction "PQ0(TOSC1)_85") (pintype "bidirectional"))
    )
    (net (code "158") (name "unconnected-(IC1-PQ1(TOSC2)-Pad86)") (class "Default")
      (node (ref "IC1") (pin "86") (pinfunction "PQ1(TOSC2)_86") (pintype "bidirectional"))
    )
    (net (code "159") (name "unconnected-(IC1-PQ2-Pad87)") (class "Default")
      (node (ref "IC1") (pin "87") (pinfunction "PQ2_87") (pintype "bidirectional"))
    )
    (net (code "160") (name "unconnected-(IC1-PQ3-Pad88)") (class "Default")
      (node (ref "IC1") (pin "88") (pinfunction "PQ3_88") (pintype "bidirectional"))
    )
    (net (code "161") (name "unconnected-(IC2-IO_VCC0-Pad3)") (class "Default")
      (node (ref "IC2") (pin "3") (pinfunction "IO_VCC0_3") (pintype "bidirectional"))
    )
    (net (code "162") (name "unconnected-(IC2-IO_VCC1-Pad4)") (class "Default")
      (node (ref "IC2") (pin "4") (pinfunction "IO_VCC1_4") (pintype "bidirectional"))
    )
    (net (code "163") (name "unconnected-(IC2-IO_VL0-Pad21)") (class "Default")
      (node (ref "IC2") (pin "21") (pinfunction "IO_VL0_21") (pintype "bidirectional"))
    )
    (net (code "164") (name "unconnected-(IC2-IO_VL1-Pad20)") (class "Default")
      (node (ref "IC2") (pin "20") (pinfunction "IO_VL1_20") (pintype "bidirectional"))
    )
    (net (code "165") (name "unconnected-(IC4-IO_VCC2-Pad5)") (class "Default")
      (node (ref "IC4") (pin "5") (pinfunction "IO_VCC2_5") (pintype "bidirectional"))
    )
    (net (code "166") (name "unconnected-(IC4-IO_VCC3-Pad6)") (class "Default")
      (node (ref "IC4") (pin "6") (pinfunction "IO_VCC3_6") (pintype "bidirectional"))
    )
    (net (code "167") (name "unconnected-(IC4-IO_VL2-Pad19)") (class "Default")
      (node (ref "IC4") (pin "19") (pinfunction "IO_VL2_19") (pintype "bidirectional"))
    )
    (net (code "168") (name "unconnected-(IC4-IO_VL3-Pad18)") (class "Default")
      (node (ref "IC4") (pin "18") (pinfunction "IO_VL3_18") (pintype "bidirectional"))
    )
    (net (code "169") (name "unconnected-(IC5-PGD-Pad3)") (class "Default")
      (node (ref "IC5") (pin "3") (pinfunction "PGD_3") (pintype "input"))
    )
    (net (code "170") (name "unconnected-(PDI_ATMEL-NC-Pad3)") (class "Default")
      (node (ref "PDI_ATMEL") (pin "3") (pinfunction "NC_3") (pintype "passive"))
    )
    (net (code "171") (name "unconnected-(PDI_ATMEL-NC.-Pad4)") (class "Default")
      (node (ref "PDI_ATMEL") (pin "4") (pinfunction "NC._4") (pintype "passive"))
    )
    (net (code "172") (name "unconnected-(SW_BATT-2-Pad1)") (class "Default")
      (node (ref "SW_BATT") (pin "1") (pinfunction "2_1") (pintype "bidirectional"))
    )
    (net (code "173") (name "unconnected-(XB1-AD0{slash}DIO0-Pad20)") (class "Default")
      (node (ref "XB1") (pin "20") (pinfunction "AD0/DIO0_20") (pintype "bidirectional"))
    )
    (net (code "174") (name "unconnected-(XB1-AD1{slash}DIO1-Pad19)") (class "Default")
      (node (ref "XB1") (pin "19") (pinfunction "AD1/DIO1_19") (pintype "bidirectional"))
    )
    (net (code "175") (name "unconnected-(XB1-AD2{slash}DIO2-Pad18)") (class "Default")
      (node (ref "XB1") (pin "18") (pinfunction "AD2/DIO2_18") (pintype "bidirectional"))
    )
    (net (code "176") (name "unconnected-(XB1-ASSOC{slash}AD5{slash}DIO5-Pad15)") (class "Default")
      (node (ref "XB1") (pin "15") (pinfunction "ASSOC/AD5/DIO5_15") (pintype "bidirectional"))
    )
    (net (code "177") (name "unconnected-(XB1-CD{slash}DOUT_EN{slash}DO8-Pad4)") (class "Default")
      (node (ref "XB1") (pin "4") (pinfunction "CD/DOUT_EN/DO8_4") (pintype "output"))
    )
    (net (code "178") (name "unconnected-(XB1-COORD_SEL{slash}AD3{slash}DIO3-Pad17)") (class "Default")
      (node (ref "XB1") (pin "17") (pinfunction "COORD_SEL/AD3/DIO3_17") (pintype "bidirectional"))
    )
    (net (code "179") (name "unconnected-(XB1-ON{slash}~{SLEEP}-Pad13)") (class "Default")
      (node (ref "XB1") (pin "13") (pinfunction "ON/~{SLEEP}_13") (pintype "output"))
    )
    (net (code "180") (name "unconnected-(XB1-PWM0{slash}RSSI-Pad6)") (class "Default")
      (node (ref "XB1") (pin "6") (pinfunction "PWM0/RSSI_6") (pintype "output"))
    )
    (net (code "181") (name "unconnected-(XB1-RF_TX{slash}AD4{slash}DIO4-Pad11)") (class "Default")
      (node (ref "XB1") (pin "11") (pinfunction "RF_TX/AD4/DIO4_11") (pintype "bidirectional"))
    )
    (net (code "182") (name "unconnected-(XB1-VREF-Pad14)") (class "Default")
      (node (ref "XB1") (pin "14") (pinfunction "VREF_14") (pintype "input"))
    )
    (net (code "183") (name "unconnected-(XB1-~{DTR}{slash}SLEEP_RQ{slash}DI8-Pad9)") (class "Default")
      (node (ref "XB1") (pin "9") (pinfunction "~{DTR}/SLEEP_RQ/DI8_9") (pintype "bidirectional"))
    )
    (net (code "184") (name "unconnected-(XB1-~{RESET}-Pad5)") (class "Default")
      (node (ref "XB1") (pin "5") (pinfunction "~{RESET}_5") (pintype "input"))
    )
  )
)
